# Guitutar.net
KiCad netlist of a schematic drawn in EAGLE
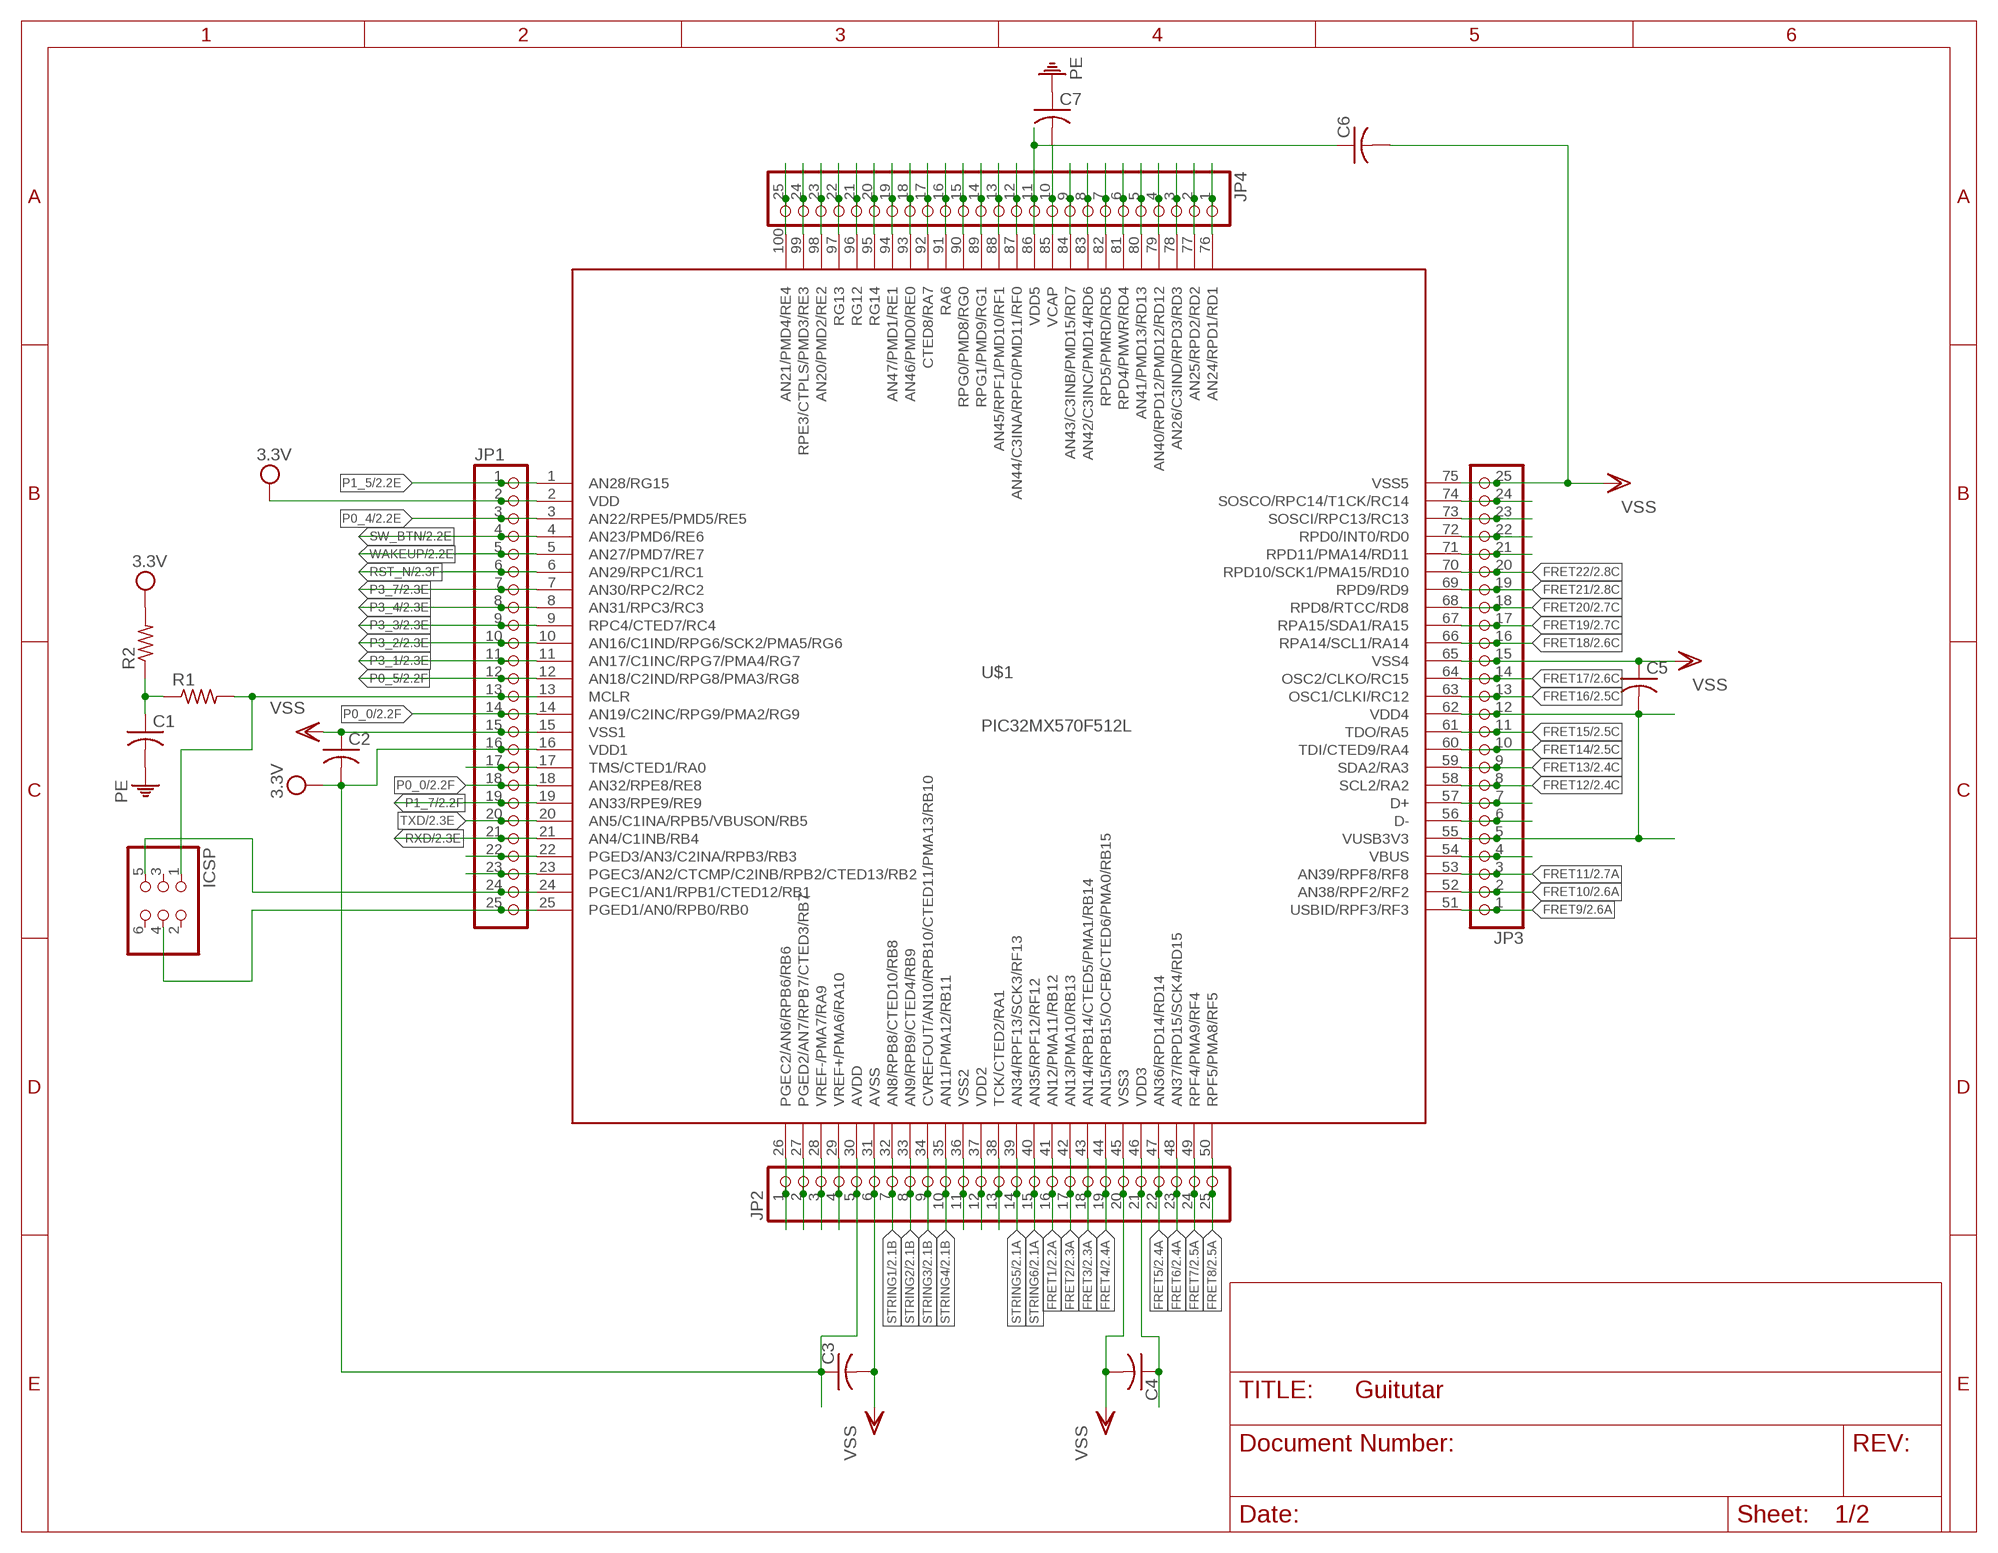
[diagram p0: schematic, sheet 1]
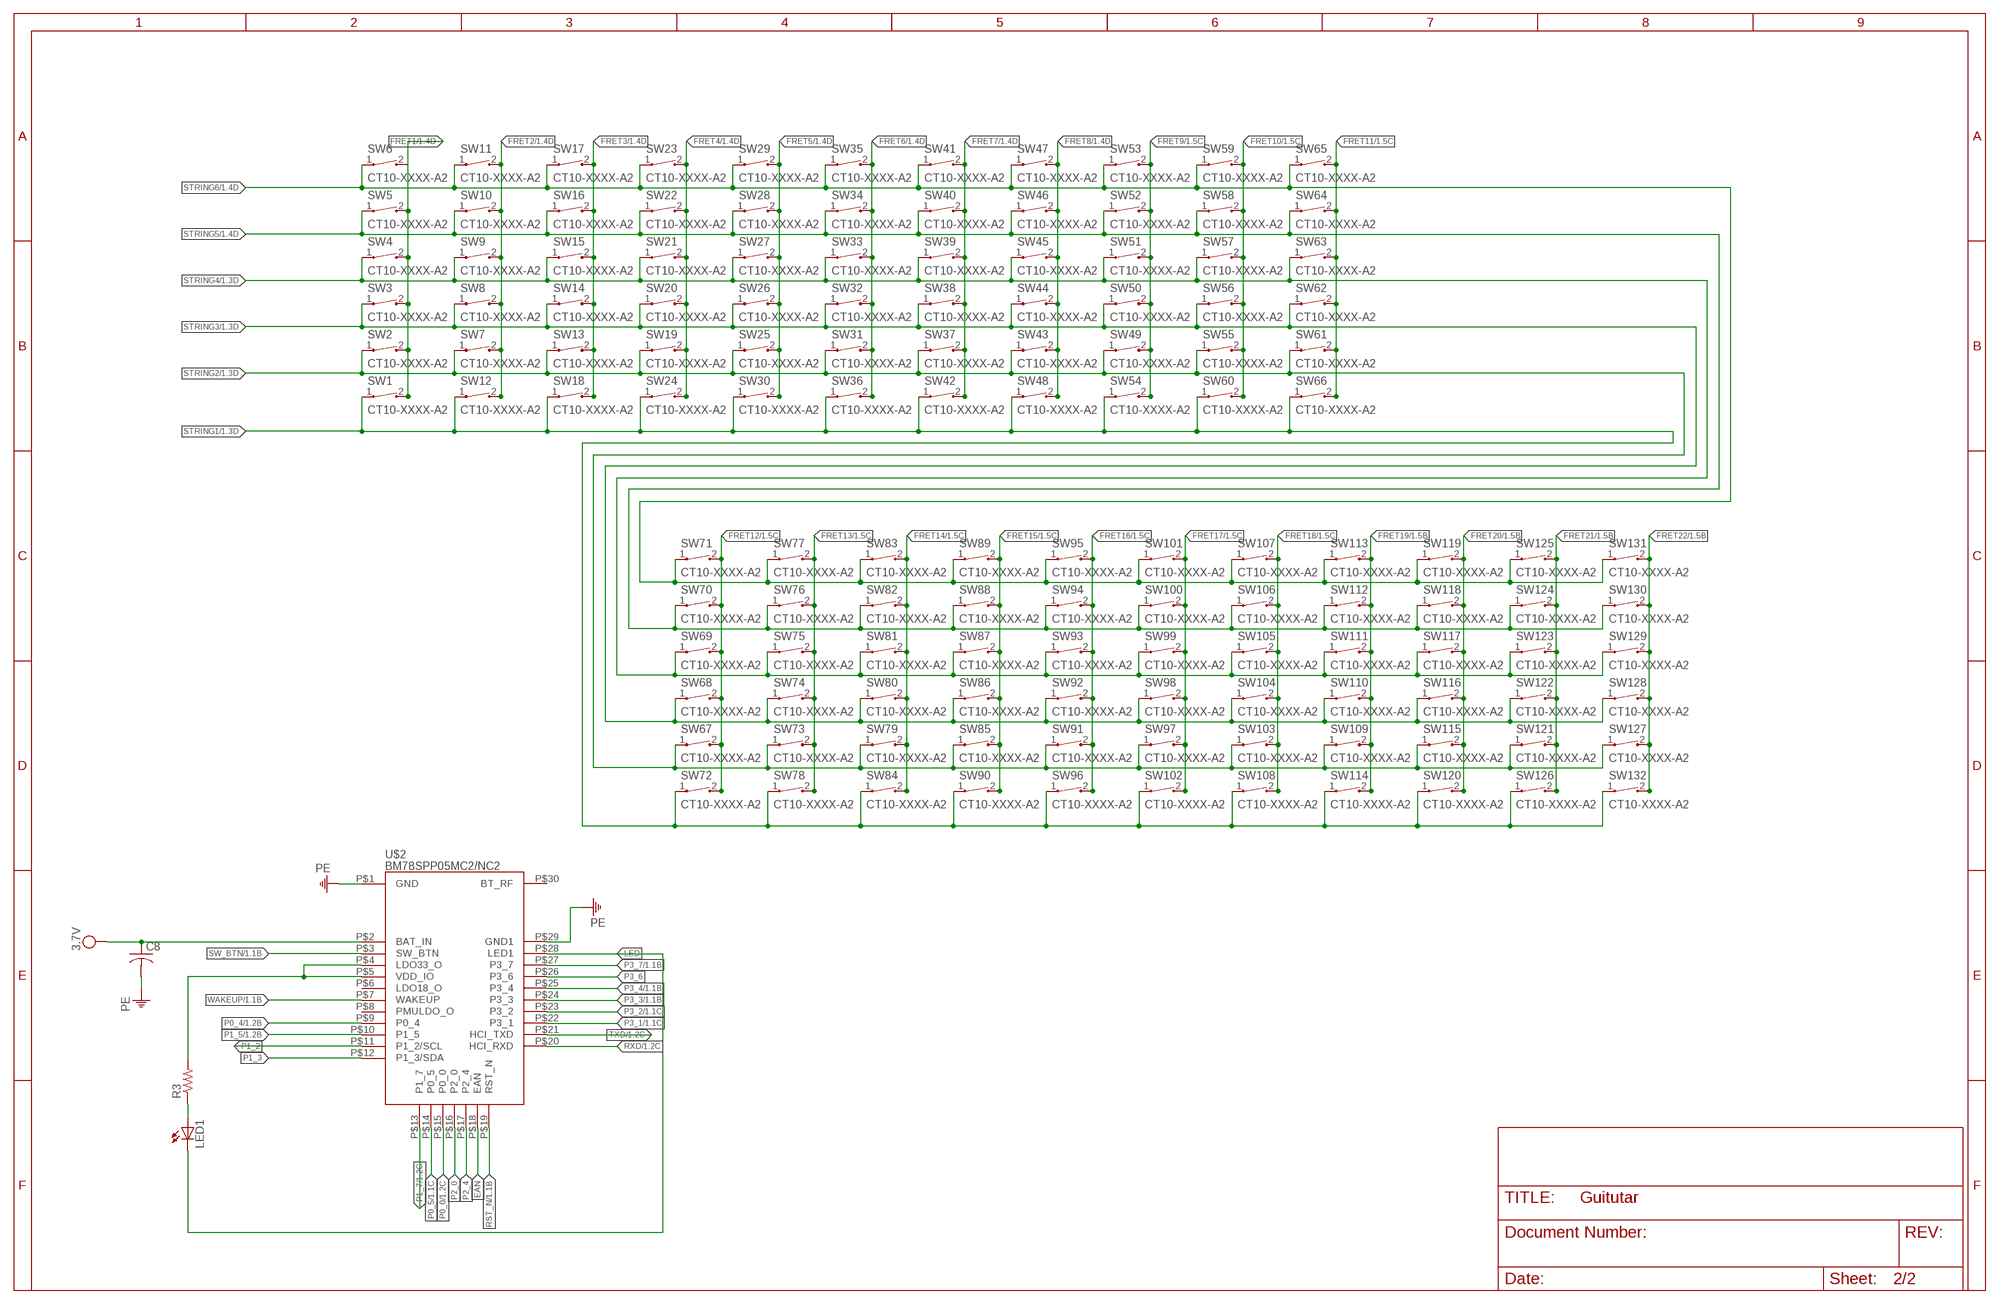
[diagram p1: schematic, sheet 2]

(export (version "E")
  (design (tool "Eeschema 10.0.6"))
  (components
    (comp (ref "C8")
      (value "C-USC0805")
      (footprint "eagle-import:C0805")
      (libsource (lib "eagle-import") (part "C-USC0805"))
    )
    (comp (ref "LED1")
      (value "LEDSMT1206")
      (footprint "eagle-import:1206")
      (libsource (lib "eagle-import") (part "LEDSMT1206"))
    )
    (comp (ref "R3")
      (value "R-US_M0805")
      (footprint "eagle-import:M0805")
      (libsource (lib "eagle-import") (part "R-US_M0805"))
    )
    (comp (ref "SW1")
      (value "CT10-XXXX-A2")
      (footprint "eagle-import:CT10-XXXX-A2")
      (libsource (lib "eagle-import") (part "CT10-XXXX-A2"))
    )
    (comp (ref "SW2")
      (value "CT10-XXXX-A2")
      (footprint "eagle-import:CT10-XXXX-A2")
      (libsource (lib "eagle-import") (part "CT10-XXXX-A2"))
    )
    (comp (ref "SW3")
      (value "CT10-XXXX-A2")
      (footprint "eagle-import:CT10-XXXX-A2")
      (libsource (lib "eagle-import") (part "CT10-XXXX-A2"))
    )
    (comp (ref "SW4")
      (value "CT10-XXXX-A2")
      (footprint "eagle-import:CT10-XXXX-A2")
      (libsource (lib "eagle-import") (part "CT10-XXXX-A2"))
    )
    (comp (ref "SW5")
      (value "CT10-XXXX-A2")
      (footprint "eagle-import:CT10-XXXX-A2")
      (libsource (lib "eagle-import") (part "CT10-XXXX-A2"))
    )
    (comp (ref "SW6")
      (value "CT10-XXXX-A2")
      (footprint "eagle-import:CT10-XXXX-A2")
      (libsource (lib "eagle-import") (part "CT10-XXXX-A2"))
    )
    (comp (ref "SW7")
      (value "CT10-XXXX-A2")
      (footprint "eagle-import:CT10-XXXX-A2")
      (libsource (lib "eagle-import") (part "CT10-XXXX-A2"))
    )
    (comp (ref "SW8")
      (value "CT10-XXXX-A2")
      (footprint "eagle-import:CT10-XXXX-A2")
      (libsource (lib "eagle-import") (part "CT10-XXXX-A2"))
    )
    (comp (ref "SW9")
      (value "CT10-XXXX-A2")
      (footprint "eagle-import:CT10-XXXX-A2")
      (libsource (lib "eagle-import") (part "CT10-XXXX-A2"))
    )
    (comp (ref "SW10")
      (value "CT10-XXXX-A2")
      (footprint "eagle-import:CT10-XXXX-A2")
      (libsource (lib "eagle-import") (part "CT10-XXXX-A2"))
    )
    (comp (ref "SW11")
      (value "CT10-XXXX-A2")
      (footprint "eagle-import:CT10-XXXX-A2")
      (libsource (lib "eagle-import") (part "CT10-XXXX-A2"))
    )
    (comp (ref "SW12")
      (value "CT10-XXXX-A2")
      (footprint "eagle-import:CT10-XXXX-A2")
      (libsource (lib "eagle-import") (part "CT10-XXXX-A2"))
    )
    (comp (ref "SW13")
      (value "CT10-XXXX-A2")
      (footprint "eagle-import:CT10-XXXX-A2")
      (libsource (lib "eagle-import") (part "CT10-XXXX-A2"))
    )
    (comp (ref "SW14")
      (value "CT10-XXXX-A2")
      (footprint "eagle-import:CT10-XXXX-A2")
      (libsource (lib "eagle-import") (part "CT10-XXXX-A2"))
    )
    (comp (ref "SW15")
      (value "CT10-XXXX-A2")
      (footprint "eagle-import:CT10-XXXX-A2")
      (libsource (lib "eagle-import") (part "CT10-XXXX-A2"))
    )
    (comp (ref "SW16")
      (value "CT10-XXXX-A2")
      (footprint "eagle-import:CT10-XXXX-A2")
      (libsource (lib "eagle-import") (part "CT10-XXXX-A2"))
    )
    (comp (ref "SW17")
      (value "CT10-XXXX-A2")
      (footprint "eagle-import:CT10-XXXX-A2")
      (libsource (lib "eagle-import") (part "CT10-XXXX-A2"))
    )
    (comp (ref "SW18")
      (value "CT10-XXXX-A2")
      (footprint "eagle-import:CT10-XXXX-A2")
      (libsource (lib "eagle-import") (part "CT10-XXXX-A2"))
    )
    (comp (ref "SW19")
      (value "CT10-XXXX-A2")
      (footprint "eagle-import:CT10-XXXX-A2")
      (libsource (lib "eagle-import") (part "CT10-XXXX-A2"))
    )
    (comp (ref "SW20")
      (value "CT10-XXXX-A2")
      (footprint "eagle-import:CT10-XXXX-A2")
      (libsource (lib "eagle-import") (part "CT10-XXXX-A2"))
    )
    (comp (ref "SW21")
      (value "CT10-XXXX-A2")
      (footprint "eagle-import:CT10-XXXX-A2")
      (libsource (lib "eagle-import") (part "CT10-XXXX-A2"))
    )
    (comp (ref "SW22")
      (value "CT10-XXXX-A2")
      (footprint "eagle-import:CT10-XXXX-A2")
      (libsource (lib "eagle-import") (part "CT10-XXXX-A2"))
    )
    (comp (ref "SW23")
      (value "CT10-XXXX-A2")
      (footprint "eagle-import:CT10-XXXX-A2")
      (libsource (lib "eagle-import") (part "CT10-XXXX-A2"))
    )
    (comp (ref "SW24")
      (value "CT10-XXXX-A2")
      (footprint "eagle-import:CT10-XXXX-A2")
      (libsource (lib "eagle-import") (part "CT10-XXXX-A2"))
    )
    (comp (ref "SW25")
      (value "CT10-XXXX-A2")
      (footprint "eagle-import:CT10-XXXX-A2")
      (libsource (lib "eagle-import") (part "CT10-XXXX-A2"))
    )
    (comp (ref "SW26")
      (value "CT10-XXXX-A2")
      (footprint "eagle-import:CT10-XXXX-A2")
      (libsource (lib "eagle-import") (part "CT10-XXXX-A2"))
    )
    (comp (ref "SW27")
      (value "CT10-XXXX-A2")
      (footprint "eagle-import:CT10-XXXX-A2")
      (libsource (lib "eagle-import") (part "CT10-XXXX-A2"))
    )
    (comp (ref "SW28")
      (value "CT10-XXXX-A2")
      (footprint "eagle-import:CT10-XXXX-A2")
      (libsource (lib "eagle-import") (part "CT10-XXXX-A2"))
    )
    (comp (ref "SW29")
      (value "CT10-XXXX-A2")
      (footprint "eagle-import:CT10-XXXX-A2")
      (libsource (lib "eagle-import") (part "CT10-XXXX-A2"))
    )
    (comp (ref "SW30")
      (value "CT10-XXXX-A2")
      (footprint "eagle-import:CT10-XXXX-A2")
      (libsource (lib "eagle-import") (part "CT10-XXXX-A2"))
    )
    (comp (ref "SW31")
      (value "CT10-XXXX-A2")
      (footprint "eagle-import:CT10-XXXX-A2")
      (libsource (lib "eagle-import") (part "CT10-XXXX-A2"))
    )
    (comp (ref "SW32")
      (value "CT10-XXXX-A2")
      (footprint "eagle-import:CT10-XXXX-A2")
      (libsource (lib "eagle-import") (part "CT10-XXXX-A2"))
    )
    (comp (ref "SW33")
      (value "CT10-XXXX-A2")
      (footprint "eagle-import:CT10-XXXX-A2")
      (libsource (lib "eagle-import") (part "CT10-XXXX-A2"))
    )
    (comp (ref "SW34")
      (value "CT10-XXXX-A2")
      (footprint "eagle-import:CT10-XXXX-A2")
      (libsource (lib "eagle-import") (part "CT10-XXXX-A2"))
    )
    (comp (ref "SW35")
      (value "CT10-XXXX-A2")
      (footprint "eagle-import:CT10-XXXX-A2")
      (libsource (lib "eagle-import") (part "CT10-XXXX-A2"))
    )
    (comp (ref "SW36")
      (value "CT10-XXXX-A2")
      (footprint "eagle-import:CT10-XXXX-A2")
      (libsource (lib "eagle-import") (part "CT10-XXXX-A2"))
    )
    (comp (ref "SW37")
      (value "CT10-XXXX-A2")
      (footprint "eagle-import:CT10-XXXX-A2")
      (libsource (lib "eagle-import") (part "CT10-XXXX-A2"))
    )
    (comp (ref "SW38")
      (value "CT10-XXXX-A2")
      (footprint "eagle-import:CT10-XXXX-A2")
      (libsource (lib "eagle-import") (part "CT10-XXXX-A2"))
    )
    (comp (ref "SW39")
      (value "CT10-XXXX-A2")
      (footprint "eagle-import:CT10-XXXX-A2")
      (libsource (lib "eagle-import") (part "CT10-XXXX-A2"))
    )
    (comp (ref "SW40")
      (value "CT10-XXXX-A2")
      (footprint "eagle-import:CT10-XXXX-A2")
      (libsource (lib "eagle-import") (part "CT10-XXXX-A2"))
    )
    (comp (ref "SW41")
      (value "CT10-XXXX-A2")
      (footprint "eagle-import:CT10-XXXX-A2")
      (libsource (lib "eagle-import") (part "CT10-XXXX-A2"))
    )
    (comp (ref "SW42")
      (value "CT10-XXXX-A2")
      (footprint "eagle-import:CT10-XXXX-A2")
      (libsource (lib "eagle-import") (part "CT10-XXXX-A2"))
    )
    (comp (ref "SW43")
      (value "CT10-XXXX-A2")
      (footprint "eagle-import:CT10-XXXX-A2")
      (libsource (lib "eagle-import") (part "CT10-XXXX-A2"))
    )
    (comp (ref "SW44")
      (value "CT10-XXXX-A2")
      (footprint "eagle-import:CT10-XXXX-A2")
      (libsource (lib "eagle-import") (part "CT10-XXXX-A2"))
    )
    (comp (ref "SW45")
      (value "CT10-XXXX-A2")
      (footprint "eagle-import:CT10-XXXX-A2")
      (libsource (lib "eagle-import") (part "CT10-XXXX-A2"))
    )
    (comp (ref "SW46")
      (value "CT10-XXXX-A2")
      (footprint "eagle-import:CT10-XXXX-A2")
      (libsource (lib "eagle-import") (part "CT10-XXXX-A2"))
    )
    (comp (ref "SW47")
      (value "CT10-XXXX-A2")
      (footprint "eagle-import:CT10-XXXX-A2")
      (libsource (lib "eagle-import") (part "CT10-XXXX-A2"))
    )
    (comp (ref "SW48")
      (value "CT10-XXXX-A2")
      (footprint "eagle-import:CT10-XXXX-A2")
      (libsource (lib "eagle-import") (part "CT10-XXXX-A2"))
    )
    (comp (ref "SW49")
      (value "CT10-XXXX-A2")
      (footprint "eagle-import:CT10-XXXX-A2")
      (libsource (lib "eagle-import") (part "CT10-XXXX-A2"))
    )
    (comp (ref "SW50")
      (value "CT10-XXXX-A2")
      (footprint "eagle-import:CT10-XXXX-A2")
      (libsource (lib "eagle-import") (part "CT10-XXXX-A2"))
    )
    (comp (ref "SW51")
      (value "CT10-XXXX-A2")
      (footprint "eagle-import:CT10-XXXX-A2")
      (libsource (lib "eagle-import") (part "CT10-XXXX-A2"))
    )
    (comp (ref "SW52")
      (value "CT10-XXXX-A2")
      (footprint "eagle-import:CT10-XXXX-A2")
      (libsource (lib "eagle-import") (part "CT10-XXXX-A2"))
    )
    (comp (ref "SW53")
      (value "CT10-XXXX-A2")
      (footprint "eagle-import:CT10-XXXX-A2")
      (libsource (lib "eagle-import") (part "CT10-XXXX-A2"))
    )
    (comp (ref "SW54")
      (value "CT10-XXXX-A2")
      (footprint "eagle-import:CT10-XXXX-A2")
      (libsource (lib "eagle-import") (part "CT10-XXXX-A2"))
    )
    (comp (ref "SW55")
      (value "CT10-XXXX-A2")
      (footprint "eagle-import:CT10-XXXX-A2")
      (libsource (lib "eagle-import") (part "CT10-XXXX-A2"))
    )
    (comp (ref "SW56")
      (value "CT10-XXXX-A2")
      (footprint "eagle-import:CT10-XXXX-A2")
      (libsource (lib "eagle-import") (part "CT10-XXXX-A2"))
    )
    (comp (ref "SW57")
      (value "CT10-XXXX-A2")
      (footprint "eagle-import:CT10-XXXX-A2")
      (libsource (lib "eagle-import") (part "CT10-XXXX-A2"))
    )
    (comp (ref "SW58")
      (value "CT10-XXXX-A2")
      (footprint "eagle-import:CT10-XXXX-A2")
      (libsource (lib "eagle-import") (part "CT10-XXXX-A2"))
    )
    (comp (ref "SW59")
      (value "CT10-XXXX-A2")
      (footprint "eagle-import:CT10-XXXX-A2")
      (libsource (lib "eagle-import") (part "CT10-XXXX-A2"))
    )
    (comp (ref "SW60")
      (value "CT10-XXXX-A2")
      (footprint "eagle-import:CT10-XXXX-A2")
      (libsource (lib "eagle-import") (part "CT10-XXXX-A2"))
    )
    (comp (ref "SW61")
      (value "CT10-XXXX-A2")
      (footprint "eagle-import:CT10-XXXX-A2")
      (libsource (lib "eagle-import") (part "CT10-XXXX-A2"))
    )
    (comp (ref "SW62")
      (value "CT10-XXXX-A2")
      (footprint "eagle-import:CT10-XXXX-A2")
      (libsource (lib "eagle-import") (part "CT10-XXXX-A2"))
    )
    (comp (ref "SW63")
      (value "CT10-XXXX-A2")
      (footprint "eagle-import:CT10-XXXX-A2")
      (libsource (lib "eagle-import") (part "CT10-XXXX-A2"))
    )
    (comp (ref "SW64")
      (value "CT10-XXXX-A2")
      (footprint "eagle-import:CT10-XXXX-A2")
      (libsource (lib "eagle-import") (part "CT10-XXXX-A2"))
    )
    (comp (ref "SW65")
      (value "CT10-XXXX-A2")
      (footprint "eagle-import:CT10-XXXX-A2")
      (libsource (lib "eagle-import") (part "CT10-XXXX-A2"))
    )
    (comp (ref "SW66")
      (value "CT10-XXXX-A2")
      (footprint "eagle-import:CT10-XXXX-A2")
      (libsource (lib "eagle-import") (part "CT10-XXXX-A2"))
    )
    (comp (ref "SW67")
      (value "CT10-XXXX-A2")
      (footprint "eagle-import:CT10-XXXX-A2")
      (libsource (lib "eagle-import") (part "CT10-XXXX-A2"))
    )
    (comp (ref "SW68")
      (value "CT10-XXXX-A2")
      (footprint "eagle-import:CT10-XXXX-A2")
      (libsource (lib "eagle-import") (part "CT10-XXXX-A2"))
    )
    (comp (ref "SW69")
      (value "CT10-XXXX-A2")
      (footprint "eagle-import:CT10-XXXX-A2")
      (libsource (lib "eagle-import") (part "CT10-XXXX-A2"))
    )
    (comp (ref "SW70")
      (value "CT10-XXXX-A2")
      (footprint "eagle-import:CT10-XXXX-A2")
      (libsource (lib "eagle-import") (part "CT10-XXXX-A2"))
    )
    (comp (ref "SW71")
      (value "CT10-XXXX-A2")
      (footprint "eagle-import:CT10-XXXX-A2")
      (libsource (lib "eagle-import") (part "CT10-XXXX-A2"))
    )
    (comp (ref "SW72")
      (value "CT10-XXXX-A2")
      (footprint "eagle-import:CT10-XXXX-A2")
      (libsource (lib "eagle-import") (part "CT10-XXXX-A2"))
    )
    (comp (ref "SW73")
      (value "CT10-XXXX-A2")
      (footprint "eagle-import:CT10-XXXX-A2")
      (libsource (lib "eagle-import") (part "CT10-XXXX-A2"))
    )
    (comp (ref "SW74")
      (value "CT10-XXXX-A2")
      (footprint "eagle-import:CT10-XXXX-A2")
      (libsource (lib "eagle-import") (part "CT10-XXXX-A2"))
    )
    (comp (ref "SW75")
      (value "CT10-XXXX-A2")
      (footprint "eagle-import:CT10-XXXX-A2")
      (libsource (lib "eagle-import") (part "CT10-XXXX-A2"))
    )
    (comp (ref "SW76")
      (value "CT10-XXXX-A2")
      (footprint "eagle-import:CT10-XXXX-A2")
      (libsource (lib "eagle-import") (part "CT10-XXXX-A2"))
    )
    (comp (ref "SW77")
      (value "CT10-XXXX-A2")
      (footprint "eagle-import:CT10-XXXX-A2")
      (libsource (lib "eagle-import") (part "CT10-XXXX-A2"))
    )
    (comp (ref "SW78")
      (value "CT10-XXXX-A2")
      (footprint "eagle-import:CT10-XXXX-A2")
      (libsource (lib "eagle-import") (part "CT10-XXXX-A2"))
    )
    (comp (ref "SW79")
      (value "CT10-XXXX-A2")
      (footprint "eagle-import:CT10-XXXX-A2")
      (libsource (lib "eagle-import") (part "CT10-XXXX-A2"))
    )
    (comp (ref "SW80")
      (value "CT10-XXXX-A2")
      (footprint "eagle-import:CT10-XXXX-A2")
      (libsource (lib "eagle-import") (part "CT10-XXXX-A2"))
    )
    (comp (ref "SW81")
      (value "CT10-XXXX-A2")
      (footprint "eagle-import:CT10-XXXX-A2")
      (libsource (lib "eagle-import") (part "CT10-XXXX-A2"))
    )
    (comp (ref "SW82")
      (value "CT10-XXXX-A2")
      (footprint "eagle-import:CT10-XXXX-A2")
      (libsource (lib "eagle-import") (part "CT10-XXXX-A2"))
    )
    (comp (ref "SW83")
      (value "CT10-XXXX-A2")
      (footprint "eagle-import:CT10-XXXX-A2")
      (libsource (lib "eagle-import") (part "CT10-XXXX-A2"))
    )
    (comp (ref "SW84")
      (value "CT10-XXXX-A2")
      (footprint "eagle-import:CT10-XXXX-A2")
      (libsource (lib "eagle-import") (part "CT10-XXXX-A2"))
    )
    (comp (ref "SW85")
      (value "CT10-XXXX-A2")
      (footprint "eagle-import:CT10-XXXX-A2")
      (libsource (lib "eagle-import") (part "CT10-XXXX-A2"))
    )
    (comp (ref "SW86")
      (value "CT10-XXXX-A2")
      (footprint "eagle-import:CT10-XXXX-A2")
      (libsource (lib "eagle-import") (part "CT10-XXXX-A2"))
    )
    (comp (ref "SW87")
      (value "CT10-XXXX-A2")
      (footprint "eagle-import:CT10-XXXX-A2")
      (libsource (lib "eagle-import") (part "CT10-XXXX-A2"))
    )
    (comp (ref "SW88")
      (value "CT10-XXXX-A2")
      (footprint "eagle-import:CT10-XXXX-A2")
      (libsource (lib "eagle-import") (part "CT10-XXXX-A2"))
    )
    (comp (ref "SW89")
      (value "CT10-XXXX-A2")
      (footprint "eagle-import:CT10-XXXX-A2")
      (libsource (lib "eagle-import") (part "CT10-XXXX-A2"))
    )
    (comp (ref "SW90")
      (value "CT10-XXXX-A2")
      (footprint "eagle-import:CT10-XXXX-A2")
      (libsource (lib "eagle-import") (part "CT10-XXXX-A2"))
    )
    (comp (ref "SW91")
      (value "CT10-XXXX-A2")
      (footprint "eagle-import:CT10-XXXX-A2")
      (libsource (lib "eagle-import") (part "CT10-XXXX-A2"))
    )
    (comp (ref "SW92")
      (value "CT10-XXXX-A2")
      (footprint "eagle-import:CT10-XXXX-A2")
      (libsource (lib "eagle-import") (part "CT10-XXXX-A2"))
    )
    (comp (ref "SW93")
      (value "CT10-XXXX-A2")
      (footprint "eagle-import:CT10-XXXX-A2")
      (libsource (lib "eagle-import") (part "CT10-XXXX-A2"))
    )
    (comp (ref "SW94")
      (value "CT10-XXXX-A2")
      (footprint "eagle-import:CT10-XXXX-A2")
      (libsource (lib "eagle-import") (part "CT10-XXXX-A2"))
    )
    (comp (ref "SW95")
      (value "CT10-XXXX-A2")
      (footprint "eagle-import:CT10-XXXX-A2")
      (libsource (lib "eagle-import") (part "CT10-XXXX-A2"))
    )
    (comp (ref "SW96")
      (value "CT10-XXXX-A2")
      (footprint "eagle-import:CT10-XXXX-A2")
      (libsource (lib "eagle-import") (part "CT10-XXXX-A2"))
    )
    (comp (ref "SW97")
      (value "CT10-XXXX-A2")
      (footprint "eagle-import:CT10-XXXX-A2")
      (libsource (lib "eagle-import") (part "CT10-XXXX-A2"))
    )
    (comp (ref "SW98")
      (value "CT10-XXXX-A2")
      (footprint "eagle-import:CT10-XXXX-A2")
      (libsource (lib "eagle-import") (part "CT10-XXXX-A2"))
    )
    (comp (ref "SW99")
      (value "CT10-XXXX-A2")
      (footprint "eagle-import:CT10-XXXX-A2")
      (libsource (lib "eagle-import") (part "CT10-XXXX-A2"))
    )
    (comp (ref "SW100")
      (value "CT10-XXXX-A2")
      (footprint "eagle-import:CT10-XXXX-A2")
      (libsource (lib "eagle-import") (part "CT10-XXXX-A2"))
    )
    (comp (ref "SW101")
      (value "CT10-XXXX-A2")
      (footprint "eagle-import:CT10-XXXX-A2")
      (libsource (lib "eagle-import") (part "CT10-XXXX-A2"))
    )
    (comp (ref "SW102")
      (value "CT10-XXXX-A2")
      (footprint "eagle-import:CT10-XXXX-A2")
      (libsource (lib "eagle-import") (part "CT10-XXXX-A2"))
    )
    (comp (ref "SW103")
      (value "CT10-XXXX-A2")
      (footprint "eagle-import:CT10-XXXX-A2")
      (libsource (lib "eagle-import") (part "CT10-XXXX-A2"))
    )
    (comp (ref "SW104")
      (value "CT10-XXXX-A2")
      (footprint "eagle-import:CT10-XXXX-A2")
      (libsource (lib "eagle-import") (part "CT10-XXXX-A2"))
    )
    (comp (ref "SW105")
      (value "CT10-XXXX-A2")
      (footprint "eagle-import:CT10-XXXX-A2")
      (libsource (lib "eagle-import") (part "CT10-XXXX-A2"))
    )
    (comp (ref "SW106")
      (value "CT10-XXXX-A2")
      (footprint "eagle-import:CT10-XXXX-A2")
      (libsource (lib "eagle-import") (part "CT10-XXXX-A2"))
    )
    (comp (ref "SW107")
      (value "CT10-XXXX-A2")
      (footprint "eagle-import:CT10-XXXX-A2")
      (libsource (lib "eagle-import") (part "CT10-XXXX-A2"))
    )
    (comp (ref "SW108")
      (value "CT10-XXXX-A2")
      (footprint "eagle-import:CT10-XXXX-A2")
      (libsource (lib "eagle-import") (part "CT10-XXXX-A2"))
    )
    (comp (ref "SW109")
      (value "CT10-XXXX-A2")
      (footprint "eagle-import:CT10-XXXX-A2")
      (libsource (lib "eagle-import") (part "CT10-XXXX-A2"))
    )
    (comp (ref "SW110")
      (value "CT10-XXXX-A2")
      (footprint "eagle-import:CT10-XXXX-A2")
      (libsource (lib "eagle-import") (part "CT10-XXXX-A2"))
    )
    (comp (ref "SW111")
      (value "CT10-XXXX-A2")
      (footprint "eagle-import:CT10-XXXX-A2")
      (libsource (lib "eagle-import") (part "CT10-XXXX-A2"))
    )
    (comp (ref "SW112")
      (value "CT10-XXXX-A2")
      (footprint "eagle-import:CT10-XXXX-A2")
      (libsource (lib "eagle-import") (part "CT10-XXXX-A2"))
    )
    (comp (ref "SW113")
      (value "CT10-XXXX-A2")
      (footprint "eagle-import:CT10-XXXX-A2")
      (libsource (lib "eagle-import") (part "CT10-XXXX-A2"))
    )
    (comp (ref "SW114")
      (value "CT10-XXXX-A2")
      (footprint "eagle-import:CT10-XXXX-A2")
      (libsource (lib "eagle-import") (part "CT10-XXXX-A2"))
    )
    (comp (ref "SW115")
      (value "CT10-XXXX-A2")
      (footprint "eagle-import:CT10-XXXX-A2")
      (libsource (lib "eagle-import") (part "CT10-XXXX-A2"))
    )
    (comp (ref "SW116")
      (value "CT10-XXXX-A2")
      (footprint "eagle-import:CT10-XXXX-A2")
      (libsource (lib "eagle-import") (part "CT10-XXXX-A2"))
    )
    (comp (ref "SW117")
      (value "CT10-XXXX-A2")
      (footprint "eagle-import:CT10-XXXX-A2")
      (libsource (lib "eagle-import") (part "CT10-XXXX-A2"))
    )
    (comp (ref "SW118")
      (value "CT10-XXXX-A2")
      (footprint "eagle-import:CT10-XXXX-A2")
      (libsource (lib "eagle-import") (part "CT10-XXXX-A2"))
    )
    (comp (ref "SW119")
      (value "CT10-XXXX-A2")
      (footprint "eagle-import:CT10-XXXX-A2")
      (libsource (lib "eagle-import") (part "CT10-XXXX-A2"))
    )
    (comp (ref "SW120")
      (value "CT10-XXXX-A2")
      (footprint "eagle-import:CT10-XXXX-A2")
      (libsource (lib "eagle-import") (part "CT10-XXXX-A2"))
    )
    (comp (ref "SW121")
      (value "CT10-XXXX-A2")
      (footprint "eagle-import:CT10-XXXX-A2")
      (libsource (lib "eagle-import") (part "CT10-XXXX-A2"))
    )
    (comp (ref "SW122")
      (value "CT10-XXXX-A2")
      (footprint "eagle-import:CT10-XXXX-A2")
      (libsource (lib "eagle-import") (part "CT10-XXXX-A2"))
    )
    (comp (ref "SW123")
      (value "CT10-XXXX-A2")
      (footprint "eagle-import:CT10-XXXX-A2")
      (libsource (lib "eagle-import") (part "CT10-XXXX-A2"))
    )
    (comp (ref "SW124")
      (value "CT10-XXXX-A2")
      (footprint "eagle-import:CT10-XXXX-A2")
      (libsource (lib "eagle-import") (part "CT10-XXXX-A2"))
    )
    (comp (ref "SW125")
      (value "CT10-XXXX-A2")
      (footprint "eagle-import:CT10-XXXX-A2")
      (libsource (lib "eagle-import") (part "CT10-XXXX-A2"))
    )
    (comp (ref "SW126")
      (value "CT10-XXXX-A2")
      (footprint "eagle-import:CT10-XXXX-A2")
      (libsource (lib "eagle-import") (part "CT10-XXXX-A2"))
    )
    (comp (ref "SW127")
      (value "CT10-XXXX-A2")
      (footprint "eagle-import:CT10-XXXX-A2")
      (libsource (lib "eagle-import") (part "CT10-XXXX-A2"))
    )
    (comp (ref "SW128")
      (value "CT10-XXXX-A2")
      (footprint "eagle-import:CT10-XXXX-A2")
      (libsource (lib "eagle-import") (part "CT10-XXXX-A2"))
    )
    (comp (ref "SW129")
      (value "CT10-XXXX-A2")
      (footprint "eagle-import:CT10-XXXX-A2")
      (libsource (lib "eagle-import") (part "CT10-XXXX-A2"))
    )
    (comp (ref "SW130")
      (value "CT10-XXXX-A2")
      (footprint "eagle-import:CT10-XXXX-A2")
      (libsource (lib "eagle-import") (part "CT10-XXXX-A2"))
    )
    (comp (ref "SW131")
      (value "CT10-XXXX-A2")
      (footprint "eagle-import:CT10-XXXX-A2")
      (libsource (lib "eagle-import") (part "CT10-XXXX-A2"))
    )
    (comp (ref "SW132")
      (value "CT10-XXXX-A2")
      (footprint "eagle-import:CT10-XXXX-A2")
      (libsource (lib "eagle-import") (part "CT10-XXXX-A2"))
    )
    (comp (ref "U$2")
      (value "BM78SPP05MC2/NC2")
      (footprint "eagle-import:BM78SPP05MC2_NC2")
      (libsource (lib "eagle-import") (part "BM78SPP05MC2/NC2"))
    )
    (comp (ref "C1")
      (value "C-USC0805")
      (footprint "eagle-import:C0805")
      (libsource (lib "eagle-import") (part "C-USC0805"))
    )
    (comp (ref "C2")
      (value "C-USC0805")
      (footprint "eagle-import:C0805")
      (libsource (lib "eagle-import") (part "C-USC0805"))
    )
    (comp (ref "C3")
      (value "C-USC0805")
      (footprint "eagle-import:C0805")
      (libsource (lib "eagle-import") (part "C-USC0805"))
    )
    (comp (ref "C4")
      (value "C-USC0805")
      (footprint "eagle-import:C0805")
      (libsource (lib "eagle-import") (part "C-USC0805"))
    )
    (comp (ref "C5")
      (value "C-USC0805")
      (footprint "eagle-import:C0805")
      (libsource (lib "eagle-import") (part "C-USC0805"))
    )
    (comp (ref "C6")
      (value "C-USC0805")
      (footprint "eagle-import:C0805")
      (libsource (lib "eagle-import") (part "C-USC0805"))
    )
    (comp (ref "C7")
      (value "C-USC0805")
      (footprint "eagle-import:C0805")
      (libsource (lib "eagle-import") (part "C-USC0805"))
    )
    (comp (ref "ICSP")
      (value "PINHD-2X3")
      (footprint "eagle-import:2X03")
      (libsource (lib "eagle-import") (part "PINHD-2X3"))
    )
    (comp (ref "JP1")
      (value "PINHD-1X25")
      (footprint "eagle-import:1X25")
      (libsource (lib "eagle-import") (part "PINHD-1X25"))
    )
    (comp (ref "JP2")
      (value "PINHD-1X25")
      (footprint "eagle-import:1X25")
      (libsource (lib "eagle-import") (part "PINHD-1X25"))
    )
    (comp (ref "JP3")
      (value "PINHD-1X25")
      (footprint "eagle-import:1X25")
      (libsource (lib "eagle-import") (part "PINHD-1X25"))
    )
    (comp (ref "JP4")
      (value "PINHD-1X25")
      (footprint "eagle-import:1X25")
      (libsource (lib "eagle-import") (part "PINHD-1X25"))
    )
    (comp (ref "R1")
      (value "R-US_M0805")
      (footprint "eagle-import:M0805")
      (libsource (lib "eagle-import") (part "R-US_M0805"))
    )
    (comp (ref "R2")
      (value "R-US_M0805")
      (footprint "eagle-import:M0805")
      (libsource (lib "eagle-import") (part "R-US_M0805"))
    )
    (comp (ref "U$1")
      (value "PIC32MX570F512L")
      (footprint "eagle-import:TQFP100-14X14")
      (libsource (lib "eagle-import") (part "PIC32MX570F512L"))
    )
  )
  (nets
    (net (code "1") (name "EAN") (class "Default")
      (node (ref "U$2") (pin "P$18") (pinfunction "EAN_P$18") (pintype "bidirectional"))
    )
    (net (code "2") (name "FRET1") (class "Default")
      (node (ref "JP2") (pin "16") (pinfunction "16_16") (pintype "passive"))
      (node (ref "SW1") (pin "2") (pinfunction "2_2") (pintype "passive"))
      (node (ref "SW2") (pin "2") (pinfunction "2_2") (pintype "passive"))
      (node (ref "SW3") (pin "2") (pinfunction "2_2") (pintype "passive"))
      (node (ref "SW4") (pin "2") (pinfunction "2_2") (pintype "passive"))
      (node (ref "SW5") (pin "2") (pinfunction "2_2") (pintype "passive"))
      (node (ref "SW6") (pin "2") (pinfunction "2_2") (pintype "passive"))
      (node (ref "U$1") (pin "41") (pinfunction "AN12/PMA11/RB12_41") (pintype "bidirectional"))
    )
    (net (code "3") (name "FRET2") (class "Default")
      (node (ref "JP2") (pin "17") (pinfunction "17_17") (pintype "passive"))
      (node (ref "SW10") (pin "2") (pinfunction "2_2") (pintype "passive"))
      (node (ref "SW11") (pin "2") (pinfunction "2_2") (pintype "passive"))
      (node (ref "SW12") (pin "2") (pinfunction "2_2") (pintype "passive"))
      (node (ref "SW7") (pin "2") (pinfunction "2_2") (pintype "passive"))
      (node (ref "SW8") (pin "2") (pinfunction "2_2") (pintype "passive"))
      (node (ref "SW9") (pin "2") (pinfunction "2_2") (pintype "passive"))
      (node (ref "U$1") (pin "42") (pinfunction "AN13/PMA10/RB13_42") (pintype "bidirectional"))
    )
    (net (code "4") (name "FRET3") (class "Default")
      (node (ref "JP2") (pin "18") (pinfunction "18_18") (pintype "passive"))
      (node (ref "SW13") (pin "2") (pinfunction "2_2") (pintype "passive"))
      (node (ref "SW14") (pin "2") (pinfunction "2_2") (pintype "passive"))
      (node (ref "SW15") (pin "2") (pinfunction "2_2") (pintype "passive"))
      (node (ref "SW16") (pin "2") (pinfunction "2_2") (pintype "passive"))
      (node (ref "SW17") (pin "2") (pinfunction "2_2") (pintype "passive"))
      (node (ref "SW18") (pin "2") (pinfunction "2_2") (pintype "passive"))
      (node (ref "U$1") (pin "43") (pinfunction "AN14/RPB14/CTED5/PMA1/RB14_43") (pintype "bidirectional"))
    )
    (net (code "5") (name "FRET4") (class "Default")
      (node (ref "JP2") (pin "19") (pinfunction "19_19") (pintype "passive"))
      (node (ref "SW19") (pin "2") (pinfunction "2_2") (pintype "passive"))
      (node (ref "SW20") (pin "2") (pinfunction "2_2") (pintype "passive"))
      (node (ref "SW21") (pin "2") (pinfunction "2_2") (pintype "passive"))
      (node (ref "SW22") (pin "2") (pinfunction "2_2") (pintype "passive"))
      (node (ref "SW23") (pin "2") (pinfunction "2_2") (pintype "passive"))
      (node (ref "SW24") (pin "2") (pinfunction "2_2") (pintype "passive"))
      (node (ref "U$1") (pin "44") (pinfunction "AN15/RPB15/OCFB/CTED6/PMA0/RB15_44") (pintype "bidirectional"))
    )
    (net (code "6") (name "FRET5") (class "Default")
      (node (ref "JP2") (pin "22") (pinfunction "22_22") (pintype "passive"))
      (node (ref "SW25") (pin "2") (pinfunction "2_2") (pintype "passive"))
      (node (ref "SW26") (pin "2") (pinfunction "2_2") (pintype "passive"))
      (node (ref "SW27") (pin "2") (pinfunction "2_2") (pintype "passive"))
      (node (ref "SW28") (pin "2") (pinfunction "2_2") (pintype "passive"))
      (node (ref "SW29") (pin "2") (pinfunction "2_2") (pintype "passive"))
      (node (ref "SW30") (pin "2") (pinfunction "2_2") (pintype "passive"))
      (node (ref "U$1") (pin "47") (pinfunction "AN36/RPD14/RD14_47") (pintype "bidirectional"))
    )
    (net (code "7") (name "FRET6") (class "Default")
      (node (ref "JP2") (pin "23") (pinfunction "23_23") (pintype "passive"))
      (node (ref "SW31") (pin "2") (pinfunction "2_2") (pintype "passive"))
      (node (ref "SW32") (pin "2") (pinfunction "2_2") (pintype "passive"))
      (node (ref "SW33") (pin "2") (pinfunction "2_2") (pintype "passive"))
      (node (ref "SW34") (pin "2") (pinfunction "2_2") (pintype "passive"))
      (node (ref "SW35") (pin "2") (pinfunction "2_2") (pintype "passive"))
      (node (ref "SW36") (pin "2") (pinfunction "2_2") (pintype "passive"))
      (node (ref "U$1") (pin "48") (pinfunction "AN37/RPD15/SCK4/RD15_48") (pintype "bidirectional"))
    )
    (net (code "8") (name "FRET7") (class "Default")
      (node (ref "JP2") (pin "24") (pinfunction "24_24") (pintype "passive"))
      (node (ref "SW37") (pin "2") (pinfunction "2_2") (pintype "passive"))
      (node (ref "SW38") (pin "2") (pinfunction "2_2") (pintype "passive"))
      (node (ref "SW39") (pin "2") (pinfunction "2_2") (pintype "passive"))
      (node (ref "SW40") (pin "2") (pinfunction "2_2") (pintype "passive"))
      (node (ref "SW41") (pin "2") (pinfunction "2_2") (pintype "passive"))
      (node (ref "SW42") (pin "2") (pinfunction "2_2") (pintype "passive"))
      (node (ref "U$1") (pin "49") (pinfunction "RPF4/PMA9/RF4_49") (pintype "bidirectional"))
    )
    (net (code "9") (name "FRET8") (class "Default")
      (node (ref "JP2") (pin "25") (pinfunction "25_25") (pintype "passive"))
      (node (ref "SW43") (pin "2") (pinfunction "2_2") (pintype "passive"))
      (node (ref "SW44") (pin "2") (pinfunction "2_2") (pintype "passive"))
      (node (ref "SW45") (pin "2") (pinfunction "2_2") (pintype "passive"))
      (node (ref "SW46") (pin "2") (pinfunction "2_2") (pintype "passive"))
      (node (ref "SW47") (pin "2") (pinfunction "2_2") (pintype "passive"))
      (node (ref "SW48") (pin "2") (pinfunction "2_2") (pintype "passive"))
      (node (ref "U$1") (pin "50") (pinfunction "RPF5/PMA8/RF5_50") (pintype "bidirectional"))
    )
    (net (code "10") (name "FRET9") (class "Default")
      (node (ref "JP3") (pin "1") (pinfunction "1_1") (pintype "passive"))
      (node (ref "SW49") (pin "2") (pinfunction "2_2") (pintype "passive"))
      (node (ref "SW50") (pin "2") (pinfunction "2_2") (pintype "passive"))
      (node (ref "SW51") (pin "2") (pinfunction "2_2") (pintype "passive"))
      (node (ref "SW52") (pin "2") (pinfunction "2_2") (pintype "passive"))
      (node (ref "SW53") (pin "2") (pinfunction "2_2") (pintype "passive"))
      (node (ref "SW54") (pin "2") (pinfunction "2_2") (pintype "passive"))
      (node (ref "U$1") (pin "51") (pinfunction "USBID/RPF3/RF3_51") (pintype "bidirectional"))
    )
    (net (code "11") (name "FRET10") (class "Default")
      (node (ref "JP3") (pin "2") (pinfunction "2_2") (pintype "passive"))
      (node (ref "SW55") (pin "2") (pinfunction "2_2") (pintype "passive"))
      (node (ref "SW56") (pin "2") (pinfunction "2_2") (pintype "passive"))
      (node (ref "SW57") (pin "2") (pinfunction "2_2") (pintype "passive"))
      (node (ref "SW58") (pin "2") (pinfunction "2_2") (pintype "passive"))
      (node (ref "SW59") (pin "2") (pinfunction "2_2") (pintype "passive"))
      (node (ref "SW60") (pin "2") (pinfunction "2_2") (pintype "passive"))
      (node (ref "U$1") (pin "52") (pinfunction "AN38/RPF2/RF2_52") (pintype "bidirectional"))
    )
    (net (code "12") (name "FRET11") (class "Default")
      (node (ref "JP3") (pin "3") (pinfunction "3_3") (pintype "passive"))
      (node (ref "SW61") (pin "2") (pinfunction "2_2") (pintype "passive"))
      (node (ref "SW62") (pin "2") (pinfunction "2_2") (pintype "passive"))
      (node (ref "SW63") (pin "2") (pinfunction "2_2") (pintype "passive"))
      (node (ref "SW64") (pin "2") (pinfunction "2_2") (pintype "passive"))
      (node (ref "SW65") (pin "2") (pinfunction "2_2") (pintype "passive"))
      (node (ref "SW66") (pin "2") (pinfunction "2_2") (pintype "passive"))
      (node (ref "U$1") (pin "53") (pinfunction "AN39/RPF8/RF8_53") (pintype "bidirectional"))
    )
    (net (code "13") (name "FRET12") (class "Default")
      (node (ref "JP3") (pin "8") (pinfunction "8_8") (pintype "passive"))
      (node (ref "SW67") (pin "2") (pinfunction "2_2") (pintype "passive"))
      (node (ref "SW68") (pin "2") (pinfunction "2_2") (pintype "passive"))
      (node (ref "SW69") (pin "2") (pinfunction "2_2") (pintype "passive"))
      (node (ref "SW70") (pin "2") (pinfunction "2_2") (pintype "passive"))
      (node (ref "SW71") (pin "2") (pinfunction "2_2") (pintype "passive"))
      (node (ref "SW72") (pin "2") (pinfunction "2_2") (pintype "passive"))
      (node (ref "U$1") (pin "58") (pinfunction "SCL2/RA2_58") (pintype "bidirectional"))
    )
    (net (code "14") (name "FRET13") (class "Default")
      (node (ref "JP3") (pin "9") (pinfunction "9_9") (pintype "passive"))
      (node (ref "SW73") (pin "2") (pinfunction "2_2") (pintype "passive"))
      (node (ref "SW74") (pin "2") (pinfunction "2_2") (pintype "passive"))
      (node (ref "SW75") (pin "2") (pinfunction "2_2") (pintype "passive"))
      (node (ref "SW76") (pin "2") (pinfunction "2_2") (pintype "passive"))
      (node (ref "SW77") (pin "2") (pinfunction "2_2") (pintype "passive"))
      (node (ref "SW78") (pin "2") (pinfunction "2_2") (pintype "passive"))
      (node (ref "U$1") (pin "59") (pinfunction "SDA2/RA3_59") (pintype "bidirectional"))
    )
    (net (code "15") (name "FRET14") (class "Default")
      (node (ref "JP3") (pin "10") (pinfunction "10_10") (pintype "passive"))
      (node (ref "SW79") (pin "2") (pinfunction "2_2") (pintype "passive"))
      (node (ref "SW80") (pin "2") (pinfunction "2_2") (pintype "passive"))
      (node (ref "SW81") (pin "2") (pinfunction "2_2") (pintype "passive"))
      (node (ref "SW82") (pin "2") (pinfunction "2_2") (pintype "passive"))
      (node (ref "SW83") (pin "2") (pinfunction "2_2") (pintype "passive"))
      (node (ref "SW84") (pin "2") (pinfunction "2_2") (pintype "passive"))
      (node (ref "U$1") (pin "60") (pinfunction "TDI/CTED9/RA4_60") (pintype "bidirectional"))
    )
    (net (code "16") (name "FRET15") (class "Default")
      (node (ref "JP3") (pin "11") (pinfunction "11_11") (pintype "passive"))
      (node (ref "SW85") (pin "2") (pinfunction "2_2") (pintype "passive"))
      (node (ref "SW86") (pin "2") (pinfunction "2_2") (pintype "passive"))
      (node (ref "SW87") (pin "2") (pinfunction "2_2") (pintype "passive"))
      (node (ref "SW88") (pin "2") (pinfunction "2_2") (pintype "passive"))
      (node (ref "SW89") (pin "2") (pinfunction "2_2") (pintype "passive"))
      (node (ref "SW90") (pin "2") (pinfunction "2_2") (pintype "passive"))
      (node (ref "U$1") (pin "61") (pinfunction "TDO/RA5_61") (pintype "bidirectional"))
    )
    (net (code "17") (name "FRET16") (class "Default")
      (node (ref "JP3") (pin "13") (pinfunction "13_13") (pintype "passive"))
      (node (ref "SW91") (pin "2") (pinfunction "2_2") (pintype "passive"))
      (node (ref "SW92") (pin "2") (pinfunction "2_2") (pintype "passive"))
      (node (ref "SW93") (pin "2") (pinfunction "2_2") (pintype "passive"))
      (node (ref "SW94") (pin "2") (pinfunction "2_2") (pintype "passive"))
      (node (ref "SW95") (pin "2") (pinfunction "2_2") (pintype "passive"))
      (node (ref "SW96") (pin "2") (pinfunction "2_2") (pintype "passive"))
      (node (ref "U$1") (pin "63") (pinfunction "OSC1/CLKI/RC12_63") (pintype "bidirectional"))
    )
    (net (code "18") (name "FRET17") (class "Default")
      (node (ref "JP3") (pin "14") (pinfunction "14_14") (pintype "passive"))
      (node (ref "SW100") (pin "2") (pinfunction "2_2") (pintype "passive"))
      (node (ref "SW101") (pin "2") (pinfunction "2_2") (pintype "passive"))
      (node (ref "SW102") (pin "2") (pinfunction "2_2") (pintype "passive"))
      (node (ref "SW97") (pin "2") (pinfunction "2_2") (pintype "passive"))
      (node (ref "SW98") (pin "2") (pinfunction "2_2") (pintype "passive"))
      (node (ref "SW99") (pin "2") (pinfunction "2_2") (pintype "passive"))
      (node (ref "U$1") (pin "64") (pinfunction "OSC2/CLKO/RC15_64") (pintype "bidirectional"))
    )
    (net (code "19") (name "FRET18") (class "Default")
      (node (ref "JP3") (pin "16") (pinfunction "16_16") (pintype "passive"))
      (node (ref "SW103") (pin "2") (pinfunction "2_2") (pintype "passive"))
      (node (ref "SW104") (pin "2") (pinfunction "2_2") (pintype "passive"))
      (node (ref "SW105") (pin "2") (pinfunction "2_2") (pintype "passive"))
      (node (ref "SW106") (pin "2") (pinfunction "2_2") (pintype "passive"))
      (node (ref "SW107") (pin "2") (pinfunction "2_2") (pintype "passive"))
      (node (ref "SW108") (pin "2") (pinfunction "2_2") (pintype "passive"))
      (node (ref "U$1") (pin "66") (pinfunction "RPA14/SCL1/RA14_66") (pintype "bidirectional"))
    )
    (net (code "20") (name "FRET19") (class "Default")
      (node (ref "JP3") (pin "17") (pinfunction "17_17") (pintype "passive"))
      (node (ref "SW109") (pin "2") (pinfunction "2_2") (pintype "passive"))
      (node (ref "SW110") (pin "2") (pinfunction "2_2") (pintype "passive"))
      (node (ref "SW111") (pin "2") (pinfunction "2_2") (pintype "passive"))
      (node (ref "SW112") (pin "2") (pinfunction "2_2") (pintype "passive"))
      (node (ref "SW113") (pin "2") (pinfunction "2_2") (pintype "passive"))
      (node (ref "SW114") (pin "2") (pinfunction "2_2") (pintype "passive"))
      (node (ref "U$1") (pin "67") (pinfunction "RPA15/SDA1/RA15_67") (pintype "bidirectional"))
    )
    (net (code "21") (name "FRET20") (class "Default")
      (node (ref "JP3") (pin "18") (pinfunction "18_18") (pintype "passive"))
      (node (ref "SW115") (pin "2") (pinfunction "2_2") (pintype "passive"))
      (node (ref "SW116") (pin "2") (pinfunction "2_2") (pintype "passive"))
      (node (ref "SW117") (pin "2") (pinfunction "2_2") (pintype "passive"))
      (node (ref "SW118") (pin "2") (pinfunction "2_2") (pintype "passive"))
      (node (ref "SW119") (pin "2") (pinfunction "2_2") (pintype "passive"))
      (node (ref "SW120") (pin "2") (pinfunction "2_2") (pintype "passive"))
      (node (ref "U$1") (pin "68") (pinfunction "RPD8/RTCC/RD8_68") (pintype "bidirectional"))
    )
    (net (code "22") (name "FRET21") (class "Default")
      (node (ref "JP3") (pin "19") (pinfunction "19_19") (pintype "passive"))
      (node (ref "SW121") (pin "2") (pinfunction "2_2") (pintype "passive"))
      (node (ref "SW122") (pin "2") (pinfunction "2_2") (pintype "passive"))
      (node (ref "SW123") (pin "2") (pinfunction "2_2") (pintype "passive"))
      (node (ref "SW124") (pin "2") (pinfunction "2_2") (pintype "passive"))
      (node (ref "SW125") (pin "2") (pinfunction "2_2") (pintype "passive"))
      (node (ref "SW126") (pin "2") (pinfunction "2_2") (pintype "passive"))
      (node (ref "U$1") (pin "69") (pinfunction "RPD9/RD9_69") (pintype "bidirectional"))
    )
    (net (code "23") (name "FRET22") (class "Default")
      (node (ref "JP3") (pin "20") (pinfunction "20_20") (pintype "passive"))
      (node (ref "SW127") (pin "2") (pinfunction "2_2") (pintype "passive"))
      (node (ref "SW128") (pin "2") (pinfunction "2_2") (pintype "passive"))
      (node (ref "SW129") (pin "2") (pinfunction "2_2") (pintype "passive"))
      (node (ref "SW130") (pin "2") (pinfunction "2_2") (pintype "passive"))
      (node (ref "SW131") (pin "2") (pinfunction "2_2") (pintype "passive"))
      (node (ref "SW132") (pin "2") (pinfunction "2_2") (pintype "passive"))
      (node (ref "U$1") (pin "70") (pinfunction "RPD10/SCK1/PMA15/RD10_70") (pintype "bidirectional"))
    )
    (net (code "24") (name "LED") (class "Default")
      (node (ref "LED1") (pin "C") (pinfunction "C_C") (pintype "passive"))
      (node (ref "U$2") (pin "P$28") (pinfunction "LED1_P$28") (pintype "bidirectional"))
    )
    (net (code "25") (name "Net-(C1-Pad1)") (class "Default")
      (node (ref "C1") (pin "1") (pinfunction "1_1") (pintype "passive"))
      (node (ref "R1") (pin "1") (pinfunction "1_1") (pintype "passive"))
      (node (ref "R2") (pin "1") (pinfunction "1_1") (pintype "passive"))
    )
    (net (code "26") (name "Net-(LED1-PadA)") (class "Default")
      (node (ref "LED1") (pin "A") (pinfunction "A_A") (pintype "passive"))
      (node (ref "R3") (pin "1") (pinfunction "1_1") (pintype "passive"))
    )
    (net (code "27") (name "Net-(U$1-AN20{slash}PMD2{slash}RE2)") (class "Default")
      (node (ref "JP4") (pin "23") (pinfunction "23_23") (pintype "passive"))
      (node (ref "U$1") (pin "98") (pinfunction "AN20/PMD2/RE2_98") (pintype "bidirectional"))
    )
    (net (code "28") (name "Net-(U$1-AN21{slash}PMD4{slash}RE4)") (class "Default")
      (node (ref "JP4") (pin "25") (pinfunction "25_25") (pintype "passive"))
      (node (ref "U$1") (pin "100") (pinfunction "AN21/PMD4/RE4_100") (pintype "bidirectional"))
    )
    (net (code "29") (name "Net-(U$1-AN24{slash}RPD1{slash}RD1)") (class "Default")
      (node (ref "JP4") (pin "1") (pinfunction "1_1") (pintype "passive"))
      (node (ref "U$1") (pin "76") (pinfunction "AN24/RPD1/RD1_76") (pintype "bidirectional"))
    )
    (net (code "30") (name "Net-(U$1-AN25{slash}RPD2{slash}RD2)") (class "Default")
      (node (ref "JP4") (pin "2") (pinfunction "2_2") (pintype "passive"))
      (node (ref "U$1") (pin "77") (pinfunction "AN25/RPD2/RD2_77") (pintype "bidirectional"))
    )
    (net (code "31") (name "Net-(U$1-AN26{slash}C3IND{slash}RPD3{slash}RD3)") (class "Default")
      (node (ref "JP4") (pin "3") (pinfunction "3_3") (pintype "passive"))
      (node (ref "U$1") (pin "78") (pinfunction "AN26/C3IND/RPD3/RD3_78") (pintype "bidirectional"))
    )
    (net (code "32") (name "Net-(U$1-AN40{slash}RPD12{slash}PMD12{slash}RD12)") (class "Default")
      (node (ref "JP4") (pin "4") (pinfunction "4_4") (pintype "passive"))
      (node (ref "U$1") (pin "79") (pinfunction "AN40/RPD12/PMD12/RD12_79") (pintype "bidirectional"))
    )
    (net (code "33") (name "Net-(U$1-AN41{slash}PMD13{slash}RD13)") (class "Default")
      (node (ref "JP4") (pin "5") (pinfunction "5_5") (pintype "passive"))
      (node (ref "U$1") (pin "80") (pinfunction "AN41/PMD13/RD13_80") (pintype "bidirectional"))
    )
    (net (code "34") (name "Net-(U$1-AN42{slash}C3INC{slash}PMD14{slash}RD6)") (class "Default")
      (node (ref "JP4") (pin "8") (pinfunction "8_8") (pintype "passive"))
      (node (ref "U$1") (pin "83") (pinfunction "AN42/C3INC/PMD14/RD6_83") (pintype "bidirectional"))
    )
    (net (code "35") (name "Net-(U$1-AN43{slash}C3INB{slash}PMD15{slash}RD7)") (class "Default")
      (node (ref "JP4") (pin "9") (pinfunction "9_9") (pintype "passive"))
      (node (ref "U$1") (pin "84") (pinfunction "AN43/C3INB/PMD15/RD7_84") (pintype "bidirectional"))
    )
    (net (code "36") (name "Net-(U$1-AN44{slash}C3INA{slash}RPF0{slash}PMD11{slash}RF0)") (class "Default")
      (node (ref "JP4") (pin "12") (pinfunction "12_12") (pintype "passive"))
      (node (ref "U$1") (pin "87") (pinfunction "AN44/C3INA/RPF0/PMD11/RF0_87") (pintype "bidirectional"))
    )
    (net (code "37") (name "Net-(U$1-AN45{slash}RPF1{slash}PMD10{slash}RF1)") (class "Default")
      (node (ref "JP4") (pin "13") (pinfunction "13_13") (pintype "passive"))
      (node (ref "U$1") (pin "88") (pinfunction "AN45/RPF1/PMD10/RF1_88") (pintype "bidirectional"))
    )
    (net (code "38") (name "Net-(U$1-AN46{slash}PMD0{slash}RE0)") (class "Default")
      (node (ref "JP4") (pin "18") (pinfunction "18_18") (pintype "passive"))
      (node (ref "U$1") (pin "93") (pinfunction "AN46/PMD0/RE0_93") (pintype "bidirectional"))
    )
    (net (code "39") (name "Net-(U$1-AN47{slash}PMD1{slash}RE1)") (class "Default")
      (node (ref "JP4") (pin "19") (pinfunction "19_19") (pintype "passive"))
      (node (ref "U$1") (pin "94") (pinfunction "AN47/PMD1/RE1_94") (pintype "bidirectional"))
    )
    (net (code "40") (name "Net-(U$1-CTED8{slash}RA7)") (class "Default")
      (node (ref "JP4") (pin "17") (pinfunction "17_17") (pintype "passive"))
      (node (ref "U$1") (pin "92") (pinfunction "CTED8/RA7_92") (pintype "bidirectional"))
    )
    (net (code "41") (name "Net-(U$1-D+)") (class "Default")
      (node (ref "JP3") (pin "7") (pinfunction "7_7") (pintype "passive"))
      (node (ref "U$1") (pin "57") (pinfunction "D+_57") (pintype "bidirectional"))
    )
    (net (code "42") (name "Net-(U$1-D-)") (class "Default")
      (node (ref "JP3") (pin "6") (pinfunction "6_6") (pintype "passive"))
      (node (ref "U$1") (pin "56") (pinfunction "D-_56") (pintype "bidirectional"))
    )
    (net (code "43") (name "Net-(U$1-MCLR)") (class "Default")
      (node (ref "ICSP") (pin "1") (pinfunction "1_1") (pintype "passive"))
      (node (ref "JP1") (pin "13") (pinfunction "13_13") (pintype "passive"))
      (node (ref "R1") (pin "2") (pinfunction "2_2") (pintype "passive"))
      (node (ref "U$1") (pin "13") (pinfunction "MCLR_13") (pintype "bidirectional"))
    )
    (net (code "44") (name "Net-(U$1-PGEC1{slash}AN1{slash}RPB1{slash}CTED12{slash}RB1)") (class "Default")
      (node (ref "ICSP") (pin "5") (pinfunction "5_5") (pintype "passive"))
      (node (ref "JP1") (pin "24") (pinfunction "24_24") (pintype "passive"))
      (node (ref "U$1") (pin "24") (pinfunction "PGEC1/AN1/RPB1/CTED12/RB1_24") (pintype "bidirectional"))
    )
    (net (code "45") (name "Net-(U$1-PGEC2{slash}AN6{slash}RPB6{slash}RB6)") (class "Default")
      (node (ref "JP2") (pin "1") (pinfunction "1_1") (pintype "passive"))
      (node (ref "U$1") (pin "26") (pinfunction "PGEC2/AN6/RPB6/RB6_26") (pintype "bidirectional"))
    )
    (net (code "46") (name "Net-(U$1-PGEC3{slash}AN2{slash}CTCMP{slash}C2INB{slash}RPB2{slash}CTED13{slash}RB2)") (class "Default")
      (node (ref "JP1") (pin "23") (pinfunction "23_23") (pintype "passive"))
      (node (ref "U$1") (pin "23") (pinfunction "PGEC3/AN2/CTCMP/C2INB/RPB2/CTED13/RB2_23") (pintype "bidirectional"))
    )
    (net (code "47") (name "Net-(U$1-PGED1{slash}AN0{slash}RPB0{slash}RB0)") (class "Default")
      (node (ref "ICSP") (pin "4") (pinfunction "4_4") (pintype "passive"))
      (node (ref "JP1") (pin "25") (pinfunction "25_25") (pintype "passive"))
      (node (ref "U$1") (pin "25") (pinfunction "PGED1/AN0/RPB0/RB0_25") (pintype "bidirectional"))
    )
    (net (code "48") (name "Net-(U$1-PGED2{slash}AN7{slash}RPB7{slash}CTED3{slash}RB7)") (class "Default")
      (node (ref "JP2") (pin "2") (pinfunction "2_2") (pintype "passive"))
      (node (ref "U$1") (pin "27") (pinfunction "PGED2/AN7/RPB7/CTED3/RB7_27") (pintype "bidirectional"))
    )
    (net (code "49") (name "Net-(U$1-PGED3{slash}AN3{slash}C2INA{slash}RPB3{slash}RB3)") (class "Default")
      (node (ref "JP1") (pin "22") (pinfunction "22_22") (pintype "passive"))
      (node (ref "U$1") (pin "22") (pinfunction "PGED3/AN3/C2INA/RPB3/RB3_22") (pintype "bidirectional"))
    )
    (net (code "50") (name "Net-(U$1-RA6)") (class "Default")
      (node (ref "JP4") (pin "16") (pinfunction "16_16") (pintype "passive"))
      (node (ref "U$1") (pin "91") (pinfunction "RA6_91") (pintype "bidirectional"))
    )
    (net (code "51") (name "Net-(U$1-RG12)") (class "Default")
      (node (ref "JP4") (pin "21") (pinfunction "21_21") (pintype "passive"))
      (node (ref "U$1") (pin "96") (pinfunction "RG12_96") (pintype "bidirectional"))
    )
    (net (code "52") (name "Net-(U$1-RG13)") (class "Default")
      (node (ref "JP4") (pin "22") (pinfunction "22_22") (pintype "passive"))
      (node (ref "U$1") (pin "97") (pinfunction "RG13_97") (pintype "bidirectional"))
    )
    (net (code "53") (name "Net-(U$1-RG14)") (class "Default")
      (node (ref "JP4") (pin "20") (pinfunction "20_20") (pintype "passive"))
      (node (ref "U$1") (pin "95") (pinfunction "RG14_95") (pintype "bidirectional"))
    )
    (net (code "54") (name "Net-(U$1-RPD0{slash}INT0{slash}RD0)") (class "Default")
      (node (ref "JP3") (pin "22") (pinfunction "22_22") (pintype "passive"))
      (node (ref "U$1") (pin "72") (pinfunction "RPD0/INT0/RD0_72") (pintype "bidirectional"))
    )
    (net (code "55") (name "Net-(U$1-RPD4{slash}PMWR{slash}RD4)") (class "Default")
      (node (ref "JP4") (pin "6") (pinfunction "6_6") (pintype "passive"))
      (node (ref "U$1") (pin "81") (pinfunction "RPD4/PMWR/RD4_81") (pintype "bidirectional"))
    )
    (net (code "56") (name "Net-(U$1-RPD5{slash}PMRD{slash}RD5)") (class "Default")
      (node (ref "JP4") (pin "7") (pinfunction "7_7") (pintype "passive"))
      (node (ref "U$1") (pin "82") (pinfunction "RPD5/PMRD/RD5_82") (pintype "bidirectional"))
    )
    (net (code "57") (name "Net-(U$1-RPD11{slash}PMA14{slash}RD11)") (class "Default")
      (node (ref "JP3") (pin "21") (pinfunction "21_21") (pintype "passive"))
      (node (ref "U$1") (pin "71") (pinfunction "RPD11/PMA14/RD11_71") (pintype "bidirectional"))
    )
    (net (code "58") (name "Net-(U$1-RPE3{slash}CTPLS{slash}PMD3{slash}RE3)") (class "Default")
      (node (ref "JP4") (pin "24") (pinfunction "24_24") (pintype "passive"))
      (node (ref "U$1") (pin "99") (pinfunction "RPE3/CTPLS/PMD3/RE3_99") (pintype "bidirectional"))
    )
    (net (code "59") (name "Net-(U$1-RPG0{slash}PMD8{slash}RG0)") (class "Default")
      (node (ref "JP4") (pin "15") (pinfunction "15_15") (pintype "passive"))
      (node (ref "U$1") (pin "90") (pinfunction "RPG0/PMD8/RG0_90") (pintype "bidirectional"))
    )
    (net (code "60") (name "Net-(U$1-RPG1{slash}PMD9{slash}RG1)") (class "Default")
      (node (ref "JP4") (pin "14") (pinfunction "14_14") (pintype "passive"))
      (node (ref "U$1") (pin "89") (pinfunction "RPG1/PMD9/RG1_89") (pintype "bidirectional"))
    )
    (net (code "61") (name "Net-(U$1-SOSCI{slash}RPC13{slash}RC13)") (class "Default")
      (node (ref "JP3") (pin "23") (pinfunction "23_23") (pintype "passive"))
      (node (ref "U$1") (pin "73") (pinfunction "SOSCI/RPC13/RC13_73") (pintype "bidirectional"))
    )
    (net (code "62") (name "Net-(U$1-SOSCO{slash}RPC14{slash}T1CK{slash}RC14)") (class "Default")
      (node (ref "JP3") (pin "24") (pinfunction "24_24") (pintype "passive"))
      (node (ref "U$1") (pin "74") (pinfunction "SOSCO/RPC14/T1CK/RC14_74") (pintype "bidirectional"))
    )
    (net (code "63") (name "Net-(U$1-TCK{slash}CTED2{slash}RA1)") (class "Default")
      (node (ref "JP2") (pin "13") (pinfunction "13_13") (pintype "passive"))
      (node (ref "U$1") (pin "38") (pinfunction "TCK/CTED2/RA1_38") (pintype "bidirectional"))
    )
    (net (code "64") (name "Net-(U$1-TMS{slash}CTED1{slash}RA0)") (class "Default")
      (node (ref "JP1") (pin "17") (pinfunction "17_17") (pintype "passive"))
      (node (ref "U$1") (pin "17") (pinfunction "TMS/CTED1/RA0_17") (pintype "bidirectional"))
    )
    (net (code "65") (name "Net-(U$1-VBUS)") (class "Default")
      (node (ref "JP3") (pin "4") (pinfunction "4_4") (pintype "passive"))
      (node (ref "U$1") (pin "54") (pinfunction "VBUS_54") (pintype "bidirectional"))
    )
    (net (code "66") (name "Net-(U$1-VCAP)") (class "Default")
      (node (ref "C7") (pin "2") (pinfunction "2_2") (pintype "passive"))
      (node (ref "JP4") (pin "10") (pinfunction "10_10") (pintype "passive"))
      (node (ref "U$1") (pin "85") (pinfunction "VCAP_85") (pintype "bidirectional"))
    )
    (net (code "67") (name "Net-(U$1-VDD2)") (class "Default")
      (node (ref "JP2") (pin "12") (pinfunction "12_12") (pintype "passive"))
      (node (ref "U$1") (pin "37") (pinfunction "VDD2_37") (pintype "bidirectional"))
    )
    (net (code "68") (name "Net-(U$1-VDD3)") (class "Default")
      (node (ref "C4") (pin "1") (pinfunction "1_1") (pintype "passive"))
      (node (ref "JP2") (pin "21") (pinfunction "21_21") (pintype "passive"))
      (node (ref "U$1") (pin "46") (pinfunction "VDD3_46") (pintype "bidirectional"))
    )
    (net (code "69") (name "Net-(U$1-VDD4)") (class "Default")
      (node (ref "C5") (pin "2") (pinfunction "2_2") (pintype "passive"))
      (node (ref "JP3") (pin "12") (pinfunction "12_12") (pintype "passive"))
      (node (ref "JP3") (pin "5") (pinfunction "5_5") (pintype "passive"))
      (node (ref "U$1") (pin "55") (pinfunction "VUSB3V3_55") (pintype "bidirectional"))
      (node (ref "U$1") (pin "62") (pinfunction "VDD4_62") (pintype "bidirectional"))
    )
    (net (code "70") (name "Net-(U$1-VDD5)") (class "Default")
      (node (ref "C6") (pin "1") (pinfunction "1_1") (pintype "passive"))
      (node (ref "JP4") (pin "11") (pinfunction "11_11") (pintype "passive"))
      (node (ref "U$1") (pin "86") (pinfunction "VDD5_86") (pintype "bidirectional"))
    )
    (net (code "71") (name "Net-(U$1-VREF+{slash}PMA6{slash}RA10)") (class "Default")
      (node (ref "JP2") (pin "4") (pinfunction "4_4") (pintype "passive"))
      (node (ref "U$1") (pin "29") (pinfunction "VREF+/PMA6/RA10_29") (pintype "bidirectional"))
    )
    (net (code "72") (name "Net-(U$1-VREF-{slash}PMA7{slash}RA9)") (class "Default")
      (node (ref "JP2") (pin "3") (pinfunction "3_3") (pintype "passive"))
      (node (ref "U$1") (pin "28") (pinfunction "VREF-/PMA7/RA9_28") (pintype "bidirectional"))
    )
    (net (code "73") (name "Net-(U$1-VSS2)") (class "Default")
      (node (ref "JP2") (pin "11") (pinfunction "11_11") (pintype "passive"))
      (node (ref "U$1") (pin "36") (pinfunction "VSS2_36") (pintype "bidirectional"))
    )
    (net (code "74") (name "Net-(U$2-LDO33_O)") (class "Default")
      (node (ref "R3") (pin "2") (pinfunction "2_2") (pintype "passive"))
      (node (ref "U$2") (pin "P$4") (pinfunction "LDO33_O_P$4") (pintype "bidirectional"))
      (node (ref "U$2") (pin "P$5") (pinfunction "VDD_IO_P$5") (pintype "bidirectional"))
    )
    (net (code "75") (name "P0_0") (class "Default")
      (node (ref "JP1") (pin "14") (pinfunction "14_14") (pintype "passive"))
      (node (ref "JP1") (pin "18") (pinfunction "18_18") (pintype "passive"))
      (node (ref "U$1") (pin "14") (pinfunction "AN19/C2INC/RPG9/PMA2/RG9_14") (pintype "bidirectional"))
      (node (ref "U$1") (pin "18") (pinfunction "AN32/RPE8/RE8_18") (pintype "bidirectional"))
      (node (ref "U$2") (pin "P$15") (pinfunction "P0_0_P$15") (pintype "bidirectional"))
    )
    (net (code "76") (name "P0_4") (class "Default")
      (node (ref "JP1") (pin "3") (pinfunction "3_3") (pintype "passive"))
      (node (ref "U$1") (pin "3") (pinfunction "AN22/RPE5/PMD5/RE5_3") (pintype "bidirectional"))
      (node (ref "U$2") (pin "P$9") (pinfunction "P0_4_P$9") (pintype "bidirectional"))
    )
    (net (code "77") (name "P0_5") (class "Default")
      (node (ref "JP1") (pin "12") (pinfunction "12_12") (pintype "passive"))
      (node (ref "U$1") (pin "12") (pinfunction "AN18/C2IND/RPG8/PMA3/RG8_12") (pintype "bidirectional"))
      (node (ref "U$2") (pin "P$14") (pinfunction "P0_5_P$14") (pintype "bidirectional"))
    )
    (net (code "78") (name "P1_2") (class "Default")
      (node (ref "U$2") (pin "P$11") (pinfunction "P1_2/SCL_P$11") (pintype "bidirectional"))
    )
    (net (code "79") (name "P1_3") (class "Default")
      (node (ref "U$2") (pin "P$12") (pinfunction "P1_3/SDA_P$12") (pintype "bidirectional"))
    )
    (net (code "80") (name "P1_5") (class "Default")
      (node (ref "JP1") (pin "1") (pinfunction "1_1") (pintype "passive"))
      (node (ref "U$1") (pin "1") (pinfunction "AN28/RG15_1") (pintype "bidirectional"))
      (node (ref "U$2") (pin "P$10") (pinfunction "P1_5_P$10") (pintype "bidirectional"))
    )
    (net (code "81") (name "P1_7") (class "Default")
      (node (ref "JP1") (pin "19") (pinfunction "19_19") (pintype "passive"))
      (node (ref "U$1") (pin "19") (pinfunction "AN33/RPE9/RE9_19") (pintype "bidirectional"))
      (node (ref "U$2") (pin "P$13") (pinfunction "P1_7_P$13") (pintype "bidirectional"))
    )
    (net (code "82") (name "P2_0") (class "Default")
      (node (ref "U$2") (pin "P$16") (pinfunction "P2_0_P$16") (pintype "bidirectional"))
    )
    (net (code "83") (name "P2_4") (class "Default")
      (node (ref "U$2") (pin "P$17") (pinfunction "P2_4_P$17") (pintype "bidirectional"))
    )
    (net (code "84") (name "P3_1") (class "Default")
      (node (ref "JP1") (pin "11") (pinfunction "11_11") (pintype "passive"))
      (node (ref "U$1") (pin "11") (pinfunction "AN17/C1INC/RPG7/PMA4/RG7_11") (pintype "bidirectional"))
      (node (ref "U$2") (pin "P$22") (pinfunction "P3_1_P$22") (pintype "bidirectional"))
    )
    (net (code "85") (name "P3_2") (class "Default")
      (node (ref "JP1") (pin "10") (pinfunction "10_10") (pintype "passive"))
      (node (ref "U$1") (pin "10") (pinfunction "AN16/C1IND/RPG6/SCK2/PMA5/RG6_10") (pintype "bidirectional"))
      (node (ref "U$2") (pin "P$23") (pinfunction "P3_2_P$23") (pintype "bidirectional"))
    )
    (net (code "86") (name "P3_3") (class "Default")
      (node (ref "JP1") (pin "9") (pinfunction "9_9") (pintype "passive"))
      (node (ref "U$1") (pin "9") (pinfunction "RPC4/CTED7/RC4_9") (pintype "bidirectional"))
      (node (ref "U$2") (pin "P$24") (pinfunction "P3_3_P$24") (pintype "bidirectional"))
    )
    (net (code "87") (name "P3_4") (class "Default")
      (node (ref "JP1") (pin "8") (pinfunction "8_8") (pintype "passive"))
      (node (ref "U$1") (pin "8") (pinfunction "AN31/RPC3/RC3_8") (pintype "bidirectional"))
      (node (ref "U$2") (pin "P$25") (pinfunction "P3_4_P$25") (pintype "bidirectional"))
    )
    (net (code "88") (name "P3_6") (class "Default")
      (node (ref "U$2") (pin "P$26") (pinfunction "P3_6_P$26") (pintype "bidirectional"))
    )
    (net (code "89") (name "P3_7") (class "Default")
      (node (ref "JP1") (pin "7") (pinfunction "7_7") (pintype "passive"))
      (node (ref "U$1") (pin "7") (pinfunction "AN30/RPC2/RC2_7") (pintype "bidirectional"))
      (node (ref "U$2") (pin "P$27") (pinfunction "P3_7_P$27") (pintype "bidirectional"))
    )
    (net (code "90") (name "PE") (class "Default")
      (node (ref "C1") (pin "2") (pinfunction "2_2") (pintype "passive"))
      (node (ref "C7") (pin "1") (pinfunction "1_1") (pintype "passive"))
      (node (ref "C8") (pin "2") (pinfunction "2_2") (pintype "passive"))
      (node (ref "U$2") (pin "P$1") (pinfunction "GND_P$1") (pintype "bidirectional"))
      (node (ref "U$2") (pin "P$29") (pinfunction "GND1_P$29") (pintype "bidirectional"))
    )
    (net (code "91") (name "RST_N") (class "Default")
      (node (ref "JP1") (pin "6") (pinfunction "6_6") (pintype "passive"))
      (node (ref "U$1") (pin "6") (pinfunction "AN29/RPC1/RC1_6") (pintype "bidirectional"))
      (node (ref "U$2") (pin "P$19") (pinfunction "RST_N_P$19") (pintype "bidirectional"))
    )
    (net (code "92") (name "RXD") (class "Default")
      (node (ref "JP1") (pin "21") (pinfunction "21_21") (pintype "passive"))
      (node (ref "U$1") (pin "21") (pinfunction "AN4/C1INB/RB4_21") (pintype "bidirectional"))
      (node (ref "U$2") (pin "P$20") (pinfunction "HCI_RXD_P$20") (pintype "bidirectional"))
    )
    (net (code "93") (name "STRING1") (class "Default")
      (node (ref "JP2") (pin "7") (pinfunction "7_7") (pintype "passive"))
      (node (ref "SW1") (pin "1") (pinfunction "1_1") (pintype "passive"))
      (node (ref "SW102") (pin "1") (pinfunction "1_1") (pintype "passive"))
      (node (ref "SW108") (pin "1") (pinfunction "1_1") (pintype "passive"))
      (node (ref "SW114") (pin "1") (pinfunction "1_1") (pintype "passive"))
      (node (ref "SW12") (pin "1") (pinfunction "1_1") (pintype "passive"))
      (node (ref "SW120") (pin "1") (pinfunction "1_1") (pintype "passive"))
      (node (ref "SW126") (pin "1") (pinfunction "1_1") (pintype "passive"))
      (node (ref "SW132") (pin "1") (pinfunction "1_1") (pintype "passive"))
      (node (ref "SW18") (pin "1") (pinfunction "1_1") (pintype "passive"))
      (node (ref "SW24") (pin "1") (pinfunction "1_1") (pintype "passive"))
      (node (ref "SW30") (pin "1") (pinfunction "1_1") (pintype "passive"))
      (node (ref "SW36") (pin "1") (pinfunction "1_1") (pintype "passive"))
      (node (ref "SW42") (pin "1") (pinfunction "1_1") (pintype "passive"))
      (node (ref "SW48") (pin "1") (pinfunction "1_1") (pintype "passive"))
      (node (ref "SW54") (pin "1") (pinfunction "1_1") (pintype "passive"))
      (node (ref "SW60") (pin "1") (pinfunction "1_1") (pintype "passive"))
      (node (ref "SW66") (pin "1") (pinfunction "1_1") (pintype "passive"))
      (node (ref "SW72") (pin "1") (pinfunction "1_1") (pintype "passive"))
      (node (ref "SW78") (pin "1") (pinfunction "1_1") (pintype "passive"))
      (node (ref "SW84") (pin "1") (pinfunction "1_1") (pintype "passive"))
      (node (ref "SW90") (pin "1") (pinfunction "1_1") (pintype "passive"))
      (node (ref "SW96") (pin "1") (pinfunction "1_1") (pintype "passive"))
      (node (ref "U$1") (pin "32") (pinfunction "AN8/RPB8/CTED10/RB8_32") (pintype "bidirectional"))
    )
    (net (code "94") (name "STRING2") (class "Default")
      (node (ref "JP2") (pin "8") (pinfunction "8_8") (pintype "passive"))
      (node (ref "SW103") (pin "1") (pinfunction "1_1") (pintype "passive"))
      (node (ref "SW109") (pin "1") (pinfunction "1_1") (pintype "passive"))
      (node (ref "SW115") (pin "1") (pinfunction "1_1") (pintype "passive"))
      (node (ref "SW121") (pin "1") (pinfunction "1_1") (pintype "passive"))
      (node (ref "SW127") (pin "1") (pinfunction "1_1") (pintype "passive"))
      (node (ref "SW13") (pin "1") (pinfunction "1_1") (pintype "passive"))
      (node (ref "SW19") (pin "1") (pinfunction "1_1") (pintype "passive"))
      (node (ref "SW2") (pin "1") (pinfunction "1_1") (pintype "passive"))
      (node (ref "SW25") (pin "1") (pinfunction "1_1") (pintype "passive"))
      (node (ref "SW31") (pin "1") (pinfunction "1_1") (pintype "passive"))
      (node (ref "SW37") (pin "1") (pinfunction "1_1") (pintype "passive"))
      (node (ref "SW43") (pin "1") (pinfunction "1_1") (pintype "passive"))
      (node (ref "SW49") (pin "1") (pinfunction "1_1") (pintype "passive"))
      (node (ref "SW55") (pin "1") (pinfunction "1_1") (pintype "passive"))
      (node (ref "SW61") (pin "1") (pinfunction "1_1") (pintype "passive"))
      (node (ref "SW67") (pin "1") (pinfunction "1_1") (pintype "passive"))
      (node (ref "SW7") (pin "1") (pinfunction "1_1") (pintype "passive"))
      (node (ref "SW73") (pin "1") (pinfunction "1_1") (pintype "passive"))
      (node (ref "SW79") (pin "1") (pinfunction "1_1") (pintype "passive"))
      (node (ref "SW85") (pin "1") (pinfunction "1_1") (pintype "passive"))
      (node (ref "SW91") (pin "1") (pinfunction "1_1") (pintype "passive"))
      (node (ref "SW97") (pin "1") (pinfunction "1_1") (pintype "passive"))
      (node (ref "U$1") (pin "33") (pinfunction "AN9/RPB9/CTED4/RB9_33") (pintype "bidirectional"))
    )
    (net (code "95") (name "STRING3") (class "Default")
      (node (ref "JP2") (pin "9") (pinfunction "9_9") (pintype "passive"))
      (node (ref "SW104") (pin "1") (pinfunction "1_1") (pintype "passive"))
      (node (ref "SW110") (pin "1") (pinfunction "1_1") (pintype "passive"))
      (node (ref "SW116") (pin "1") (pinfunction "1_1") (pintype "passive"))
      (node (ref "SW122") (pin "1") (pinfunction "1_1") (pintype "passive"))
      (node (ref "SW128") (pin "1") (pinfunction "1_1") (pintype "passive"))
      (node (ref "SW14") (pin "1") (pinfunction "1_1") (pintype "passive"))
      (node (ref "SW20") (pin "1") (pinfunction "1_1") (pintype "passive"))
      (node (ref "SW26") (pin "1") (pinfunction "1_1") (pintype "passive"))
      (node (ref "SW3") (pin "1") (pinfunction "1_1") (pintype "passive"))
      (node (ref "SW32") (pin "1") (pinfunction "1_1") (pintype "passive"))
      (node (ref "SW38") (pin "1") (pinfunction "1_1") (pintype "passive"))
      (node (ref "SW44") (pin "1") (pinfunction "1_1") (pintype "passive"))
      (node (ref "SW50") (pin "1") (pinfunction "1_1") (pintype "passive"))
      (node (ref "SW56") (pin "1") (pinfunction "1_1") (pintype "passive"))
      (node (ref "SW62") (pin "1") (pinfunction "1_1") (pintype "passive"))
      (node (ref "SW68") (pin "1") (pinfunction "1_1") (pintype "passive"))
      (node (ref "SW74") (pin "1") (pinfunction "1_1") (pintype "passive"))
      (node (ref "SW8") (pin "1") (pinfunction "1_1") (pintype "passive"))
      (node (ref "SW80") (pin "1") (pinfunction "1_1") (pintype "passive"))
      (node (ref "SW86") (pin "1") (pinfunction "1_1") (pintype "passive"))
      (node (ref "SW92") (pin "1") (pinfunction "1_1") (pintype "passive"))
      (node (ref "SW98") (pin "1") (pinfunction "1_1") (pintype "passive"))
      (node (ref "U$1") (pin "34") (pinfunction "CVREFOUT/AN10/RPB10/CTED11/PMA13/RB10_34") (pintype "bidirectional"))
    )
    (net (code "96") (name "STRING4") (class "Default")
      (node (ref "JP2") (pin "10") (pinfunction "10_10") (pintype "passive"))
      (node (ref "SW105") (pin "1") (pinfunction "1_1") (pintype "passive"))
      (node (ref "SW111") (pin "1") (pinfunction "1_1") (pintype "passive"))
      (node (ref "SW117") (pin "1") (pinfunction "1_1") (pintype "passive"))
      (node (ref "SW123") (pin "1") (pinfunction "1_1") (pintype "passive"))
      (node (ref "SW129") (pin "1") (pinfunction "1_1") (pintype "passive"))
      (node (ref "SW15") (pin "1") (pinfunction "1_1") (pintype "passive"))
      (node (ref "SW21") (pin "1") (pinfunction "1_1") (pintype "passive"))
      (node (ref "SW27") (pin "1") (pinfunction "1_1") (pintype "passive"))
      (node (ref "SW33") (pin "1") (pinfunction "1_1") (pintype "passive"))
      (node (ref "SW39") (pin "1") (pinfunction "1_1") (pintype "passive"))
      (node (ref "SW4") (pin "1") (pinfunction "1_1") (pintype "passive"))
      (node (ref "SW45") (pin "1") (pinfunction "1_1") (pintype "passive"))
      (node (ref "SW51") (pin "1") (pinfunction "1_1") (pintype "passive"))
      (node (ref "SW57") (pin "1") (pinfunction "1_1") (pintype "passive"))
      (node (ref "SW63") (pin "1") (pinfunction "1_1") (pintype "passive"))
      (node (ref "SW69") (pin "1") (pinfunction "1_1") (pintype "passive"))
      (node (ref "SW75") (pin "1") (pinfunction "1_1") (pintype "passive"))
      (node (ref "SW81") (pin "1") (pinfunction "1_1") (pintype "passive"))
      (node (ref "SW87") (pin "1") (pinfunction "1_1") (pintype "passive"))
      (node (ref "SW9") (pin "1") (pinfunction "1_1") (pintype "passive"))
      (node (ref "SW93") (pin "1") (pinfunction "1_1") (pintype "passive"))
      (node (ref "SW99") (pin "1") (pinfunction "1_1") (pintype "passive"))
      (node (ref "U$1") (pin "35") (pinfunction "AN11/PMA12/RB11_35") (pintype "bidirectional"))
    )
    (net (code "97") (name "STRING5") (class "Default")
      (node (ref "JP2") (pin "14") (pinfunction "14_14") (pintype "passive"))
      (node (ref "SW10") (pin "1") (pinfunction "1_1") (pintype "passive"))
      (node (ref "SW100") (pin "1") (pinfunction "1_1") (pintype "passive"))
      (node (ref "SW106") (pin "1") (pinfunction "1_1") (pintype "passive"))
      (node (ref "SW112") (pin "1") (pinfunction "1_1") (pintype "passive"))
      (node (ref "SW118") (pin "1") (pinfunction "1_1") (pintype "passive"))
      (node (ref "SW124") (pin "1") (pinfunction "1_1") (pintype "passive"))
      (node (ref "SW130") (pin "1") (pinfunction "1_1") (pintype "passive"))
      (node (ref "SW16") (pin "1") (pinfunction "1_1") (pintype "passive"))
      (node (ref "SW22") (pin "1") (pinfunction "1_1") (pintype "passive"))
      (node (ref "SW28") (pin "1") (pinfunction "1_1") (pintype "passive"))
      (node (ref "SW34") (pin "1") (pinfunction "1_1") (pintype "passive"))
      (node (ref "SW40") (pin "1") (pinfunction "1_1") (pintype "passive"))
      (node (ref "SW46") (pin "1") (pinfunction "1_1") (pintype "passive"))
      (node (ref "SW5") (pin "1") (pinfunction "1_1") (pintype "passive"))
      (node (ref "SW52") (pin "1") (pinfunction "1_1") (pintype "passive"))
      (node (ref "SW58") (pin "1") (pinfunction "1_1") (pintype "passive"))
      (node (ref "SW64") (pin "1") (pinfunction "1_1") (pintype "passive"))
      (node (ref "SW70") (pin "1") (pinfunction "1_1") (pintype "passive"))
      (node (ref "SW76") (pin "1") (pinfunction "1_1") (pintype "passive"))
      (node (ref "SW82") (pin "1") (pinfunction "1_1") (pintype "passive"))
      (node (ref "SW88") (pin "1") (pinfunction "1_1") (pintype "passive"))
      (node (ref "SW94") (pin "1") (pinfunction "1_1") (pintype "passive"))
      (node (ref "U$1") (pin "39") (pinfunction "AN34/RPF13/SCK3/RF13_39") (pintype "bidirectional"))
    )
    (net (code "98") (name "STRING6") (class "Default")
      (node (ref "JP2") (pin "15") (pinfunction "15_15") (pintype "passive"))
      (node (ref "SW101") (pin "1") (pinfunction "1_1") (pintype "passive"))
      (node (ref "SW107") (pin "1") (pinfunction "1_1") (pintype "passive"))
      (node (ref "SW11") (pin "1") (pinfunction "1_1") (pintype "passive"))
      (node (ref "SW113") (pin "1") (pinfunction "1_1") (pintype "passive"))
      (node (ref "SW119") (pin "1") (pinfunction "1_1") (pintype "passive"))
      (node (ref "SW125") (pin "1") (pinfunction "1_1") (pintype "passive"))
      (node (ref "SW131") (pin "1") (pinfunction "1_1") (pintype "passive"))
      (node (ref "SW17") (pin "1") (pinfunction "1_1") (pintype "passive"))
      (node (ref "SW23") (pin "1") (pinfunction "1_1") (pintype "passive"))
      (node (ref "SW29") (pin "1") (pinfunction "1_1") (pintype "passive"))
      (node (ref "SW35") (pin "1") (pinfunction "1_1") (pintype "passive"))
      (node (ref "SW41") (pin "1") (pinfunction "1_1") (pintype "passive"))
      (node (ref "SW47") (pin "1") (pinfunction "1_1") (pintype "passive"))
      (node (ref "SW53") (pin "1") (pinfunction "1_1") (pintype "passive"))
      (node (ref "SW59") (pin "1") (pinfunction "1_1") (pintype "passive"))
      (node (ref "SW6") (pin "1") (pinfunction "1_1") (pintype "passive"))
      (node (ref "SW65") (pin "1") (pinfunction "1_1") (pintype "passive"))
      (node (ref "SW71") (pin "1") (pinfunction "1_1") (pintype "passive"))
      (node (ref "SW77") (pin "1") (pinfunction "1_1") (pintype "passive"))
      (node (ref "SW83") (pin "1") (pinfunction "1_1") (pintype "passive"))
      (node (ref "SW89") (pin "1") (pinfunction "1_1") (pintype "passive"))
      (node (ref "SW95") (pin "1") (pinfunction "1_1") (pintype "passive"))
      (node (ref "U$1") (pin "40") (pinfunction "AN35/RPF12/RF12_40") (pintype "bidirectional"))
    )
    (net (code "99") (name "SW_BTN") (class "Default")
      (node (ref "JP1") (pin "4") (pinfunction "4_4") (pintype "passive"))
      (node (ref "U$1") (pin "4") (pinfunction "AN23/PMD6/RE6_4") (pintype "bidirectional"))
      (node (ref "U$2") (pin "P$3") (pinfunction "SW_BTN_P$3") (pintype "bidirectional"))
    )
    (net (code "100") (name "TXD") (class "Default")
      (node (ref "JP1") (pin "20") (pinfunction "20_20") (pintype "passive"))
      (node (ref "U$1") (pin "20") (pinfunction "AN5/C1INA/RPB5/VBUSON/RB5_20") (pintype "bidirectional"))
      (node (ref "U$2") (pin "P$21") (pinfunction "HCI_TXD_P$21") (pintype "bidirectional"))
    )
    (net (code "101") (name "VDD") (class "Default")
      (node (ref "C2") (pin "2") (pinfunction "2_2") (pintype "passive"))
      (node (ref "C3") (pin "1") (pinfunction "1_1") (pintype "passive"))
      (node (ref "C8") (pin "1") (pinfunction "1_1") (pintype "passive"))
      (node (ref "JP1") (pin "16") (pinfunction "16_16") (pintype "passive"))
      (node (ref "JP1") (pin "2") (pinfunction "2_2") (pintype "passive"))
      (node (ref "JP2") (pin "5") (pinfunction "5_5") (pintype "passive"))
      (node (ref "R2") (pin "2") (pinfunction "2_2") (pintype "passive"))
      (node (ref "U$1") (pin "16") (pinfunction "VDD1_16") (pintype "bidirectional"))
      (node (ref "U$1") (pin "2") (pinfunction "VDD_2") (pintype "bidirectional"))
      (node (ref "U$1") (pin "30") (pinfunction "AVDD_30") (pintype "bidirectional"))
      (node (ref "U$2") (pin "P$2") (pinfunction "BAT_IN_P$2") (pintype "bidirectional"))
    )
    (net (code "102") (name "VSS") (class "Default")
      (node (ref "C2") (pin "1") (pinfunction "1_1") (pintype "passive"))
      (node (ref "C3") (pin "2") (pinfunction "2_2") (pintype "passive"))
      (node (ref "C4") (pin "2") (pinfunction "2_2") (pintype "passive"))
      (node (ref "C5") (pin "1") (pinfunction "1_1") (pintype "passive"))
      (node (ref "C6") (pin "2") (pinfunction "2_2") (pintype "passive"))
      (node (ref "JP1") (pin "15") (pinfunction "15_15") (pintype "passive"))
      (node (ref "JP2") (pin "20") (pinfunction "20_20") (pintype "passive"))
      (node (ref "JP2") (pin "6") (pinfunction "6_6") (pintype "passive"))
      (node (ref "JP3") (pin "15") (pinfunction "15_15") (pintype "passive"))
      (node (ref "JP3") (pin "25") (pinfunction "25_25") (pintype "passive"))
      (node (ref "U$1") (pin "15") (pinfunction "VSS1_15") (pintype "bidirectional"))
      (node (ref "U$1") (pin "31") (pinfunction "AVSS_31") (pintype "bidirectional"))
      (node (ref "U$1") (pin "45") (pinfunction "VSS3_45") (pintype "bidirectional"))
      (node (ref "U$1") (pin "65") (pinfunction "VSS4_65") (pintype "bidirectional"))
      (node (ref "U$1") (pin "75") (pinfunction "VSS5_75") (pintype "bidirectional"))
    )
    (net (code "103") (name "WAKEUP") (class "Default")
      (node (ref "JP1") (pin "5") (pinfunction "5_5") (pintype "passive"))
      (node (ref "U$1") (pin "5") (pinfunction "AN27/PMD7/RE7_5") (pintype "bidirectional"))
      (node (ref "U$2") (pin "P$7") (pinfunction "WAKEUP_P$7") (pintype "bidirectional"))
    )
    (net (code "104") (name "unconnected-(ICSP-Pad2)") (class "Default")
      (node (ref "ICSP") (pin "2") (pinfunction "2_2") (pintype "passive"))
    )
    (net (code "105") (name "unconnected-(ICSP-Pad3)") (class "Default")
      (node (ref "ICSP") (pin "3") (pinfunction "3_3") (pintype "passive"))
    )
    (net (code "106") (name "unconnected-(ICSP-Pad6)") (class "Default")
      (node (ref "ICSP") (pin "6") (pinfunction "6_6") (pintype "passive"))
    )
    (net (code "107") (name "unconnected-(U$2-BT_RF-PadP$30)") (class "Default")
      (node (ref "U$2") (pin "P$30") (pinfunction "BT_RF_P$30") (pintype "bidirectional"))
    )
    (net (code "108") (name "unconnected-(U$2-LDO18_O-PadP$6)") (class "Default")
      (node (ref "U$2") (pin "P$6") (pinfunction "LDO18_O_P$6") (pintype "bidirectional"))
    )
    (net (code "109") (name "unconnected-(U$2-PMULDO_O-PadP$8)") (class "Default")
      (node (ref "U$2") (pin "P$8") (pinfunction "PMULDO_O_P$8") (pintype "bidirectional"))
    )
  )
)
